# IBL_behavior_control.net
KiCad netlist of a schematic drawn in EAGLE
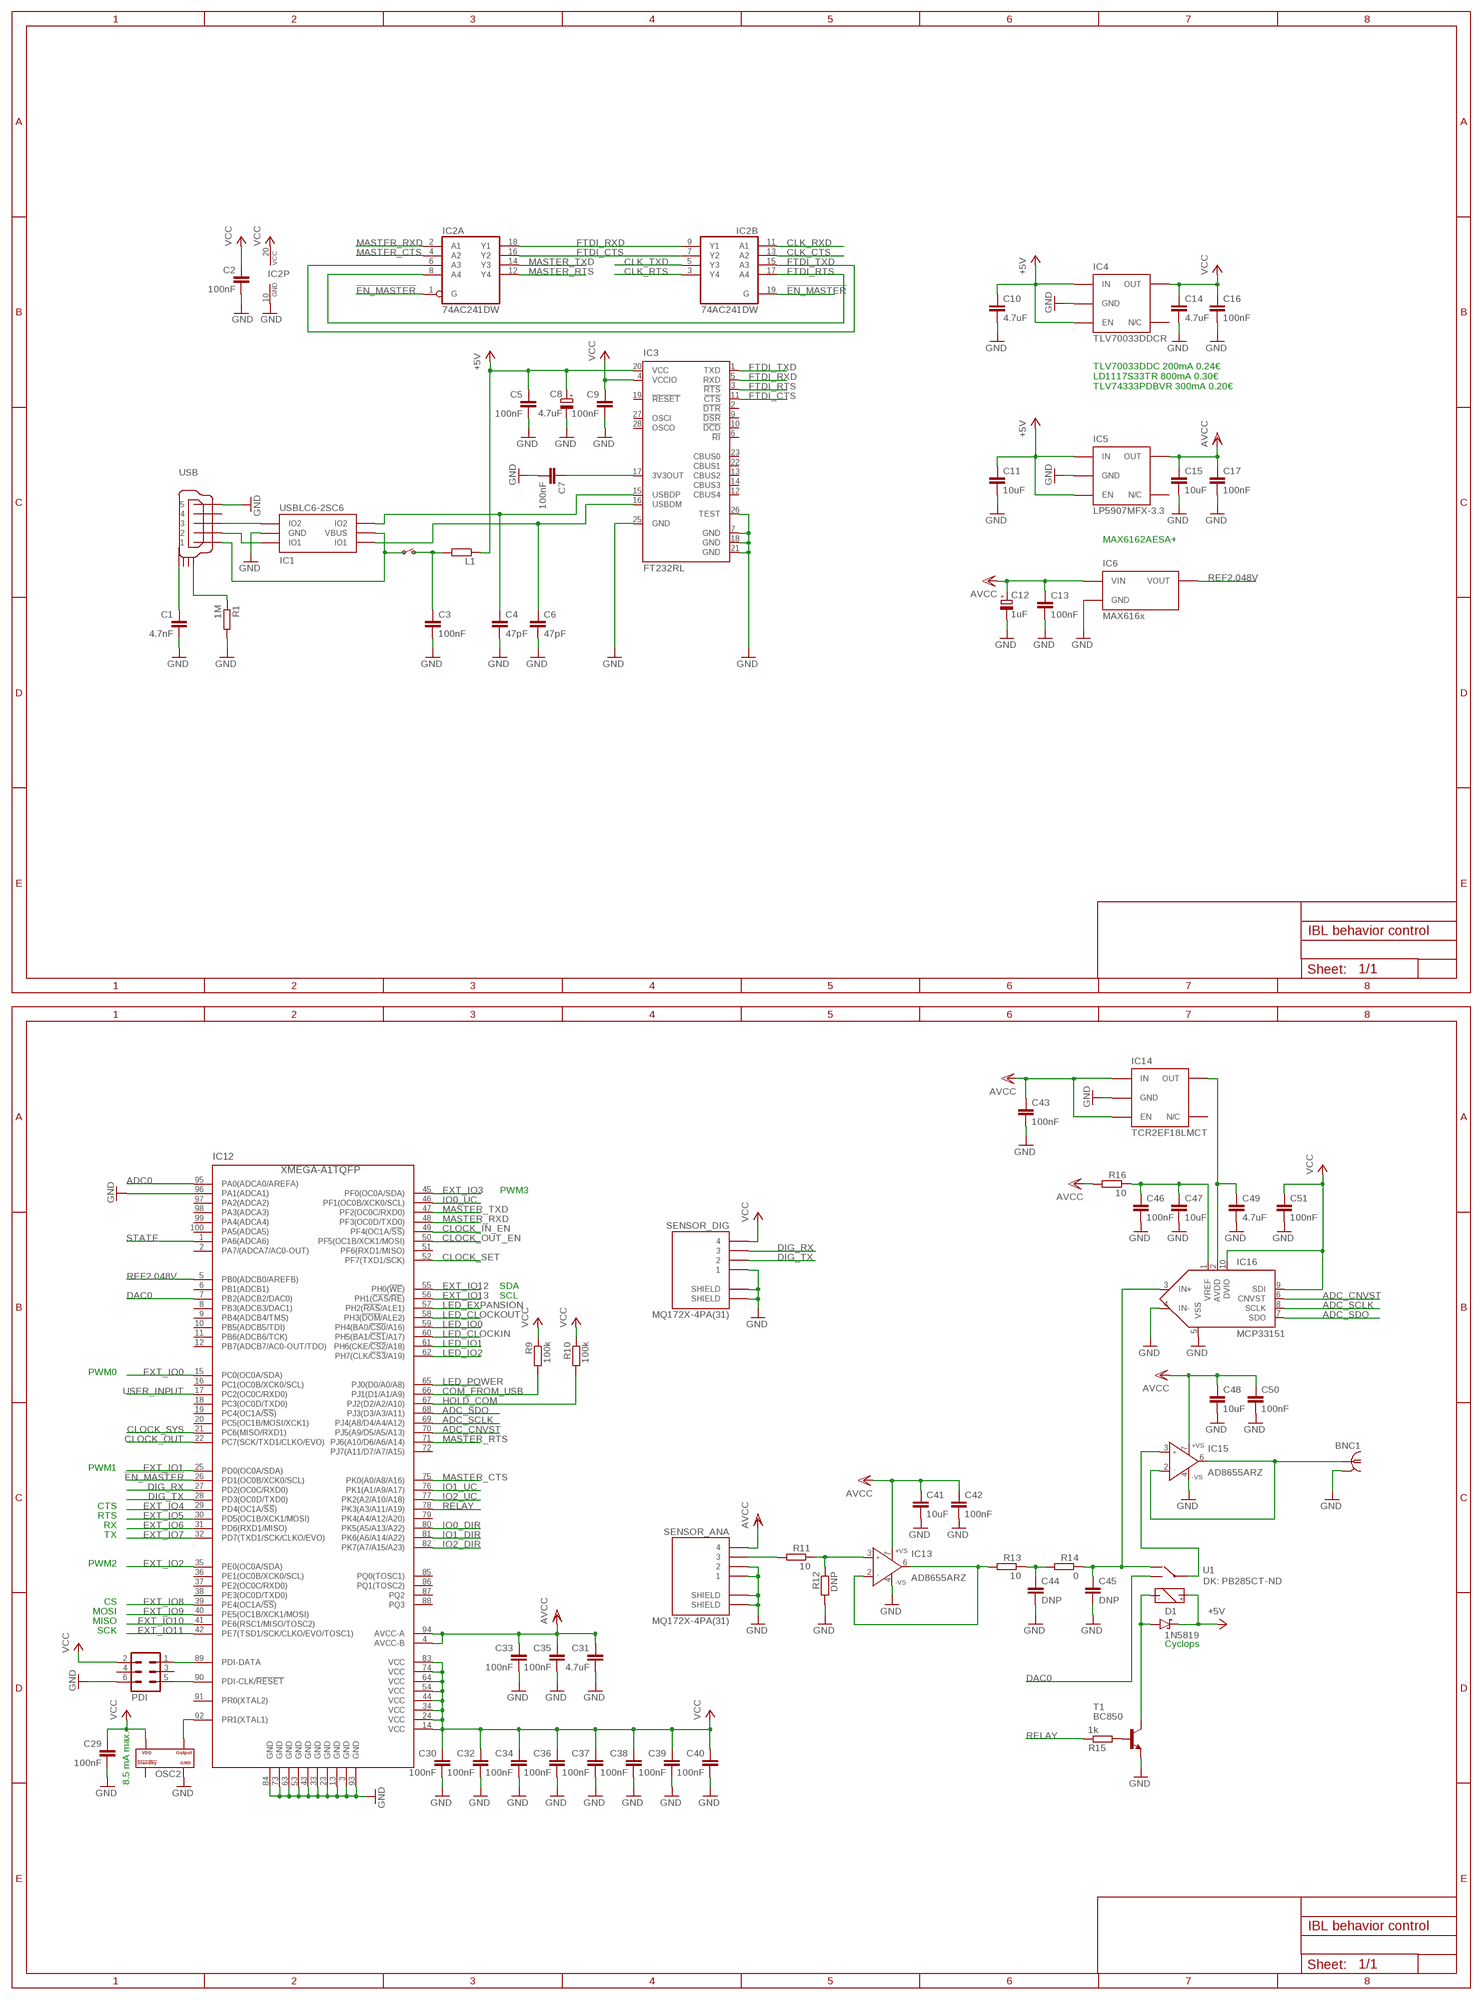
[diagram p0: schematic, sheet 1, part 1 of 2]
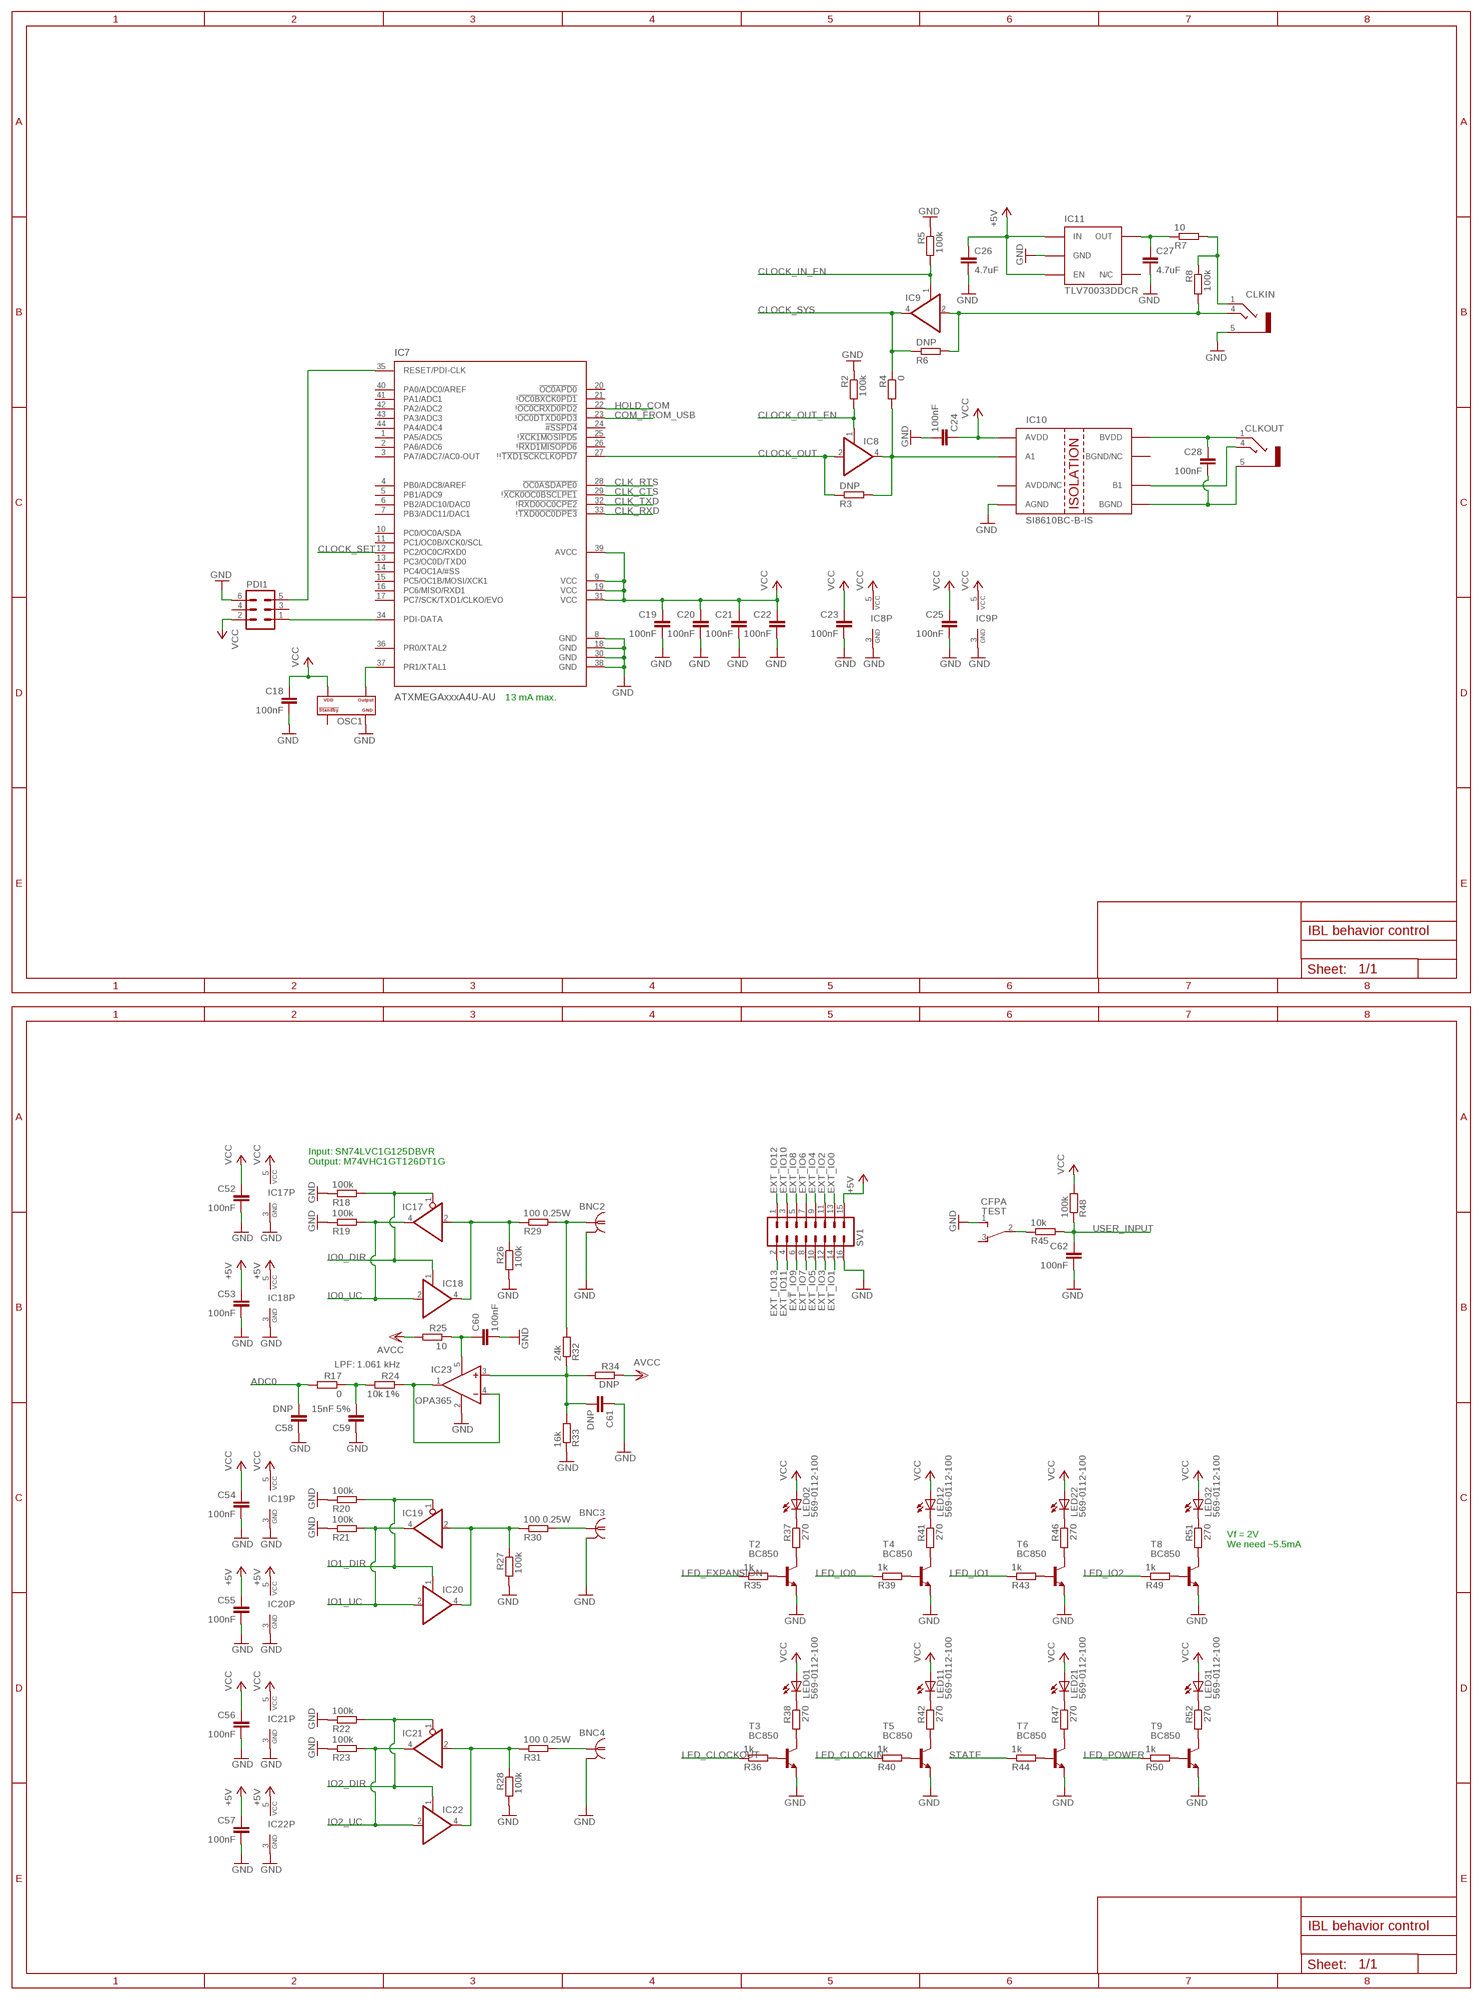
[diagram p1: schematic, sheet 1, part 2 of 2]

(export (version "E")
  (design (tool "Eeschema 10.0.6"))
  (components
    (comp (ref "BNC1")
      (value "BNC_0731000105")
      (footprint "eagle-import:0731000105")
      (libsource (lib "eagle-import") (part "BNC_0731000105"))
    )
    (comp (ref "BNC2")
      (value "BNC_0731000105")
      (footprint "eagle-import:0731000105")
      (libsource (lib "eagle-import") (part "BNC_0731000105"))
    )
    (comp (ref "BNC3")
      (value "BNC_0731000105")
      (footprint "eagle-import:0731000105")
      (libsource (lib "eagle-import") (part "BNC_0731000105"))
    )
    (comp (ref "BNC4")
      (value "BNC_0731000105")
      (footprint "eagle-import:0731000105")
      (libsource (lib "eagle-import") (part "BNC_0731000105"))
    )
    (comp (ref "C1")
      (value "4.7nF")
      (footprint "eagle-import:C0402")
      (libsource (lib "eagle-import") (part "C-EUC0402"))
    )
    (comp (ref "C2")
      (value "100nF")
      (footprint "eagle-import:C0402")
      (libsource (lib "eagle-import") (part "C-EUC0402"))
    )
    (comp (ref "C3")
      (value "100nF")
      (footprint "eagle-import:C0402")
      (libsource (lib "eagle-import") (part "C-EUC0402"))
    )
    (comp (ref "C4")
      (value "47pF")
      (footprint "eagle-import:C0402")
      (libsource (lib "eagle-import") (part "C-EUC0402"))
    )
    (comp (ref "C5")
      (value "100nF")
      (footprint "eagle-import:C0402")
      (libsource (lib "eagle-import") (part "C-EUC0402"))
    )
    (comp (ref "C6")
      (value "47pF")
      (footprint "eagle-import:C0402")
      (libsource (lib "eagle-import") (part "C-EUC0402"))
    )
    (comp (ref "C7")
      (value "100nF")
      (footprint "eagle-import:C0402")
      (libsource (lib "eagle-import") (part "C-EUC0402"))
    )
    (comp (ref "C8")
      (value "4.7uF")
      (footprint "eagle-import:A_3216-18W")
      (libsource (lib "eagle-import") (part "CPOL-EUA/3216-18W"))
    )
    (comp (ref "C9")
      (value "100nF")
      (footprint "eagle-import:C0402")
      (libsource (lib "eagle-import") (part "C-EUC0402"))
    )
    (comp (ref "C10")
      (value "4.7uF")
      (footprint "eagle-import:C0603")
      (libsource (lib "eagle-import") (part "C-EUC0603"))
    )
    (comp (ref "C11")
      (value "10uF")
      (footprint "eagle-import:C0603")
      (libsource (lib "eagle-import") (part "C-EUC0603"))
    )
    (comp (ref "C12")
      (value "1uF")
      (footprint "eagle-import:R_2012-12R")
      (libsource (lib "eagle-import") (part "CPOL-EUR/2012-12R"))
    )
    (comp (ref "C13")
      (value "100nF")
      (footprint "eagle-import:C0402")
      (libsource (lib "eagle-import") (part "C-EUC0402"))
    )
    (comp (ref "C14")
      (value "4.7uF")
      (footprint "eagle-import:C0603")
      (libsource (lib "eagle-import") (part "C-EUC0603"))
    )
    (comp (ref "C15")
      (value "10uF")
      (footprint "eagle-import:C0603")
      (libsource (lib "eagle-import") (part "C-EUC0603"))
    )
    (comp (ref "C16")
      (value "100nF")
      (footprint "eagle-import:C0402")
      (libsource (lib "eagle-import") (part "C-EUC0402"))
    )
    (comp (ref "C17")
      (value "100nF")
      (footprint "eagle-import:C0402")
      (libsource (lib "eagle-import") (part "C-EUC0402"))
    )
    (comp (ref "C18")
      (value "100nF")
      (footprint "eagle-import:C0402")
      (libsource (lib "eagle-import") (part "C-EUC0402"))
    )
    (comp (ref "C19")
      (value "100nF")
      (footprint "eagle-import:C0402")
      (libsource (lib "eagle-import") (part "C-EUC0402"))
    )
    (comp (ref "C20")
      (value "100nF")
      (footprint "eagle-import:C0402")
      (libsource (lib "eagle-import") (part "C-EUC0402"))
    )
    (comp (ref "C21")
      (value "100nF")
      (footprint "eagle-import:C0402")
      (libsource (lib "eagle-import") (part "C-EUC0402"))
    )
    (comp (ref "C22")
      (value "100nF")
      (footprint "eagle-import:C0402")
      (libsource (lib "eagle-import") (part "C-EUC0402"))
    )
    (comp (ref "C23")
      (value "100nF")
      (footprint "eagle-import:C0402")
      (libsource (lib "eagle-import") (part "C-EUC0402"))
    )
    (comp (ref "C24")
      (value "100nF")
      (footprint "eagle-import:C0402")
      (libsource (lib "eagle-import") (part "C-EUC0402"))
    )
    (comp (ref "C25")
      (value "100nF")
      (footprint "eagle-import:C0402")
      (libsource (lib "eagle-import") (part "C-EUC0402"))
    )
    (comp (ref "C26")
      (value "4.7uF")
      (footprint "eagle-import:C0603")
      (libsource (lib "eagle-import") (part "C-EUC0603"))
    )
    (comp (ref "C27")
      (value "4.7uF")
      (footprint "eagle-import:C0603")
      (libsource (lib "eagle-import") (part "C-EUC0603"))
    )
    (comp (ref "C28")
      (value "100nF")
      (footprint "eagle-import:C0402")
      (libsource (lib "eagle-import") (part "C-EUC0402"))
    )
    (comp (ref "C29")
      (value "100nF")
      (footprint "eagle-import:C0402")
      (libsource (lib "eagle-import") (part "C-EUC0402"))
    )
    (comp (ref "C30")
      (value "100nF")
      (footprint "eagle-import:C0402")
      (libsource (lib "eagle-import") (part "C-EUC0402"))
    )
    (comp (ref "C31")
      (value "4.7uF")
      (footprint "eagle-import:C0603")
      (libsource (lib "eagle-import") (part "C-EUC0603"))
    )
    (comp (ref "C32")
      (value "100nF")
      (footprint "eagle-import:C0402")
      (libsource (lib "eagle-import") (part "C-EUC0402"))
    )
    (comp (ref "C33")
      (value "100nF")
      (footprint "eagle-import:C0402")
      (libsource (lib "eagle-import") (part "C-EUC0402"))
    )
    (comp (ref "C34")
      (value "100nF")
      (footprint "eagle-import:C0402")
      (libsource (lib "eagle-import") (part "C-EUC0402"))
    )
    (comp (ref "C35")
      (value "100nF")
      (footprint "eagle-import:C0402")
      (libsource (lib "eagle-import") (part "C-EUC0402"))
    )
    (comp (ref "C36")
      (value "100nF")
      (footprint "eagle-import:C0402")
      (libsource (lib "eagle-import") (part "C-EUC0402"))
    )
    (comp (ref "C37")
      (value "100nF")
      (footprint "eagle-import:C0402")
      (libsource (lib "eagle-import") (part "C-EUC0402"))
    )
    (comp (ref "C38")
      (value "100nF")
      (footprint "eagle-import:C0402")
      (libsource (lib "eagle-import") (part "C-EUC0402"))
    )
    (comp (ref "C39")
      (value "100nF")
      (footprint "eagle-import:C0402")
      (libsource (lib "eagle-import") (part "C-EUC0402"))
    )
    (comp (ref "C40")
      (value "100nF")
      (footprint "eagle-import:C0402")
      (libsource (lib "eagle-import") (part "C-EUC0402"))
    )
    (comp (ref "C41")
      (value "10uF")
      (footprint "eagle-import:C0603")
      (libsource (lib "eagle-import") (part "C-EUC0603"))
    )
    (comp (ref "C42")
      (value "100nF")
      (footprint "eagle-import:C0402")
      (libsource (lib "eagle-import") (part "C-EUC0402"))
    )
    (comp (ref "C43")
      (value "100nF")
      (footprint "eagle-import:C0402")
      (libsource (lib "eagle-import") (part "C-EUC0402"))
    )
    (comp (ref "C44")
      (value "DNP")
      (footprint "eagle-import:C0402")
      (libsource (lib "eagle-import") (part "C-EUC0402"))
    )
    (comp (ref "C45")
      (value "DNP")
      (footprint "eagle-import:C0402")
      (libsource (lib "eagle-import") (part "C-EUC0402"))
    )
    (comp (ref "C46")
      (value "100nF")
      (footprint "eagle-import:C0402")
      (libsource (lib "eagle-import") (part "C-EUC0402"))
    )
    (comp (ref "C47")
      (value "10uF")
      (footprint "eagle-import:C0603")
      (libsource (lib "eagle-import") (part "C-EUC0603"))
    )
    (comp (ref "C48")
      (value "10uF")
      (footprint "eagle-import:C0603")
      (libsource (lib "eagle-import") (part "C-EUC0603"))
    )
    (comp (ref "C49")
      (value "4.7uF")
      (footprint "eagle-import:C0603")
      (libsource (lib "eagle-import") (part "C-EUC0603"))
    )
    (comp (ref "C50")
      (value "100nF")
      (footprint "eagle-import:C0402")
      (libsource (lib "eagle-import") (part "C-EUC0402"))
    )
    (comp (ref "C51")
      (value "100nF")
      (footprint "eagle-import:C0402")
      (libsource (lib "eagle-import") (part "C-EUC0402"))
    )
    (comp (ref "C52")
      (value "100nF")
      (footprint "eagle-import:C0402")
      (libsource (lib "eagle-import") (part "C-EUC0402"))
    )
    (comp (ref "C53")
      (value "100nF")
      (footprint "eagle-import:C0402")
      (libsource (lib "eagle-import") (part "C-EUC0402"))
    )
    (comp (ref "C54")
      (value "100nF")
      (footprint "eagle-import:C0402")
      (libsource (lib "eagle-import") (part "C-EUC0402"))
    )
    (comp (ref "C55")
      (value "100nF")
      (footprint "eagle-import:C0402")
      (libsource (lib "eagle-import") (part "C-EUC0402"))
    )
    (comp (ref "C56")
      (value "100nF")
      (footprint "eagle-import:C0402")
      (libsource (lib "eagle-import") (part "C-EUC0402"))
    )
    (comp (ref "C57")
      (value "100nF")
      (footprint "eagle-import:C0402")
      (libsource (lib "eagle-import") (part "C-EUC0402"))
    )
    (comp (ref "C58")
      (value "DNP")
      (footprint "eagle-import:C0402")
      (libsource (lib "eagle-import") (part "C-EUC0402"))
    )
    (comp (ref "C59")
      (value "15nF 5%")
      (footprint "eagle-import:C0402")
      (libsource (lib "eagle-import") (part "C-EUC0402"))
    )
    (comp (ref "C60")
      (value "100nF")
      (footprint "eagle-import:C0402")
      (libsource (lib "eagle-import") (part "C-EUC0402"))
    )
    (comp (ref "C61")
      (value "DNP")
      (footprint "eagle-import:C0402")
      (libsource (lib "eagle-import") (part "C-EUC0402"))
    )
    (comp (ref "C62")
      (value "100nF")
      (footprint "eagle-import:C0402")
      (libsource (lib "eagle-import") (part "C-EUC0402"))
    )
    (comp (ref "CLKIN")
      (value "STEREO_JACK")
      (footprint "eagle-import:35RASMT2BHNTRX")
      (libsource (lib "eagle-import") (part "STEREO_JACK"))
    )
    (comp (ref "CLKOUT")
      (value "STEREO_JACK")
      (footprint "eagle-import:35RASMT2BHNTRX")
      (libsource (lib "eagle-import") (part "STEREO_JACK"))
    )
    (comp (ref "D1")
      (value "1N5819")
      (footprint "eagle-import:SOD123")
      (libsource (lib "eagle-import") (part "S-DIODESOD-123"))
    )
    (comp (ref "IC1")
      (value "USBLC6-2SC6")
      (footprint "eagle-import:SOT23-6L")
      (libsource (lib "eagle-import") (part "USBLC6-2"))
    )
    (comp (ref "IC2")
      (value "74AC241DW")
      (footprint "eagle-import:SO20W")
      (libsource (lib "eagle-import") (part "74241DWAC"))
    )
    (comp (ref "IC3")
      (value "FT232RL")
      (footprint "eagle-import:SSOP28")
      (libsource (lib "eagle-import") (part "FT232RL"))
    )
    (comp (ref "IC4")
      (value "TLV70033DDCR")
      (footprint "eagle-import:TSOT23-5")
      (libsource (lib "eagle-import") (part "TLV700XX"))
    )
    (comp (ref "IC5")
      (value "LP5907MFX-3.3")
      (footprint "eagle-import:TSOT23-5")
      (libsource (lib "eagle-import") (part "TLV700XX"))
    )
    (comp (ref "IC6")
      (value "MAX616x")
      (footprint "eagle-import:SO-08")
      (libsource (lib "eagle-import") (part "ADR45XX"))
    )
    (comp (ref "IC7")
      (value "ATXMEGAxxxA4U-AU")
      (footprint "eagle-import:QFP80P1200X1200X120-44N")
      (libsource (lib "eagle-import") (part "AT-XMEGA-XXA4-AU"))
    )
    (comp (ref "IC8")
      (value "74AHC1G126DCK")
      (footprint "eagle-import:SC70-5")
      (libsource (lib "eagle-import") (part "741G126DCKAHC"))
    )
    (comp (ref "IC9")
      (value "74AHC1G126DCK")
      (footprint "eagle-import:SC70-5")
      (libsource (lib "eagle-import") (part "741G126DCKAHC"))
    )
    (comp (ref "IC10")
      (value "SI8610BC-B-IS")
      (footprint "eagle-import:SO-08")
      (libsource (lib "eagle-import") (part "SI8610"))
    )
    (comp (ref "IC11")
      (value "TLV70033DDCR")
      (footprint "eagle-import:TSOT23-5")
      (libsource (lib "eagle-import") (part "TLV700XX"))
    )
    (comp (ref "IC12")
      (value "XMEGA-A1TQFP")
      (footprint "eagle-import:TQFP100")
      (libsource (lib "eagle-import") (part "XMEGA-A1TQFP"))
    )
    (comp (ref "IC13")
      (value "AD8655ARZ")
      (footprint "eagle-import:SO8")
      (fields (field (name "MF") "ALTERA CORPORATION") (field (name "MPN") "AD8655ARMZ-REEL"))
      (libsource (lib "eagle-import") (part "AD8655R"))
    )
    (comp (ref "IC14")
      (value "TCR2EF18LMCT")
      (footprint "eagle-import:TSOT23-5")
      (libsource (lib "eagle-import") (part "TLV700XX"))
    )
    (comp (ref "IC15")
      (value "AD8655ARZ")
      (footprint "eagle-import:SO8")
      (fields (field (name "MF") "ALTERA CORPORATION") (field (name "MPN") "AD8655ARMZ-REEL"))
      (libsource (lib "eagle-import") (part "AD8655R"))
    )
    (comp (ref "IC16")
      (value "MCP33151")
      (footprint "eagle-import:MSOP10")
      (libsource (lib "eagle-import") (part "MCP33151"))
    )
    (comp (ref "IC17")
      (value "74AHC1G125DBV")
      (footprint "eagle-import:SOT23-5")
      (libsource (lib "eagle-import") (part "741G125DBVAHC"))
    )
    (comp (ref "IC18")
      (value "74AHC1G126DCK")
      (footprint "eagle-import:SC70-5")
      (libsource (lib "eagle-import") (part "741G126DCKAHC"))
    )
    (comp (ref "IC19")
      (value "74AHC1G125DBV")
      (footprint "eagle-import:SOT23-5")
      (libsource (lib "eagle-import") (part "741G125DBVAHC"))
    )
    (comp (ref "IC20")
      (value "74AHC1G126DCK")
      (footprint "eagle-import:SC70-5")
      (libsource (lib "eagle-import") (part "741G126DCKAHC"))
    )
    (comp (ref "IC21")
      (value "74AHC1G125DBV")
      (footprint "eagle-import:SOT23-5")
      (libsource (lib "eagle-import") (part "741G125DBVAHC"))
    )
    (comp (ref "IC22")
      (value "74AHC1G126DCK")
      (footprint "eagle-import:SC70-5")
      (libsource (lib "eagle-import") (part "741G126DCKAHC"))
    )
    (comp (ref "IC23")
      (value "OPA365")
      (footprint "eagle-import:SOT23-5")
      (libsource (lib "eagle-import") (part "OPA365"))
    )
    (comp (ref "L1")
      (value "???")
      (footprint "eagle-import:R0805")
      (libsource (lib "eagle-import") (part "R-EU_R0805"))
    )
    (comp (ref "LED0")
      (value "569-0112-100")
      (footprint "eagle-import:569-011X-X00_LED_ARRAY")
      (libsource (lib "eagle-import") (part "LED_2X_VERTICAL"))
    )
    (comp (ref "LED1")
      (value "569-0112-100")
      (footprint "eagle-import:569-011X-X00_LED_ARRAY")
      (libsource (lib "eagle-import") (part "LED_2X_VERTICAL"))
    )
    (comp (ref "LED2")
      (value "569-0112-100")
      (footprint "eagle-import:569-011X-X00_LED_ARRAY")
      (libsource (lib "eagle-import") (part "LED_2X_VERTICAL"))
    )
    (comp (ref "LED3")
      (value "569-0112-100")
      (footprint "eagle-import:569-011X-X00_LED_ARRAY")
      (libsource (lib "eagle-import") (part "LED_2X_VERTICAL"))
    )
    (comp (ref "OSC1")
      (value "OSCILLATOR")
      (footprint "eagle-import:OSCILLATOR_3.2X2.5")
      (libsource (lib "eagle-import") (part "OSCILLATOR"))
    )
    (comp (ref "OSC2")
      (value "OSCILLATOR")
      (footprint "eagle-import:OSCILLATOR_3.2X2.5")
      (libsource (lib "eagle-import") (part "OSCILLATOR"))
    )
    (comp (ref "PDI")
      (value "MA03-2")
      (footprint "eagle-import:MA03-2")
      (libsource (lib "eagle-import") (part "MA03-2"))
    )
    (comp (ref "PDI1")
      (value "MA03-2")
      (footprint "eagle-import:MA03-2")
      (libsource (lib "eagle-import") (part "MA03-2"))
    )
    (comp (ref "R1")
      (value "1M")
      (footprint "eagle-import:R0402")
      (libsource (lib "eagle-import") (part "R-EU_R0402"))
    )
    (comp (ref "R2")
      (value "100k")
      (footprint "eagle-import:R0402")
      (libsource (lib "eagle-import") (part "R-EU_R0402"))
    )
    (comp (ref "R3")
      (value "DNP")
      (footprint "eagle-import:R0402")
      (libsource (lib "eagle-import") (part "R-EU_R0402"))
    )
    (comp (ref "R4")
      (value "0")
      (footprint "eagle-import:R0402")
      (libsource (lib "eagle-import") (part "R-EU_R0402"))
    )
    (comp (ref "R5")
      (value "100k")
      (footprint "eagle-import:R0402")
      (libsource (lib "eagle-import") (part "R-EU_R0402"))
    )
    (comp (ref "R6")
      (value "DNP")
      (footprint "eagle-import:R0402")
      (libsource (lib "eagle-import") (part "R-EU_R0402"))
    )
    (comp (ref "R7")
      (value "10")
      (footprint "eagle-import:R0402")
      (libsource (lib "eagle-import") (part "R-EU_R0402"))
    )
    (comp (ref "R8")
      (value "100k")
      (footprint "eagle-import:R0402")
      (libsource (lib "eagle-import") (part "R-EU_R0402"))
    )
    (comp (ref "R9")
      (value "100k")
      (footprint "eagle-import:R0402")
      (libsource (lib "eagle-import") (part "R-EU_R0402"))
    )
    (comp (ref "R10")
      (value "100k")
      (footprint "eagle-import:R0402")
      (libsource (lib "eagle-import") (part "R-EU_R0402"))
    )
    (comp (ref "R11")
      (value "10")
      (footprint "eagle-import:R0402")
      (libsource (lib "eagle-import") (part "R-EU_R0402"))
    )
    (comp (ref "R12")
      (value "DNP")
      (footprint "eagle-import:R0402")
      (libsource (lib "eagle-import") (part "R-EU_R0402"))
    )
    (comp (ref "R13")
      (value "10")
      (footprint "eagle-import:R0402")
      (libsource (lib "eagle-import") (part "R-EU_R0402"))
    )
    (comp (ref "R14")
      (value "0")
      (footprint "eagle-import:R0402")
      (libsource (lib "eagle-import") (part "R-EU_R0402"))
    )
    (comp (ref "R15")
      (value "1k")
      (footprint "eagle-import:R0402")
      (libsource (lib "eagle-import") (part "R-EU_R0402"))
    )
    (comp (ref "R16")
      (value "10")
      (footprint "eagle-import:R0402")
      (libsource (lib "eagle-import") (part "R-EU_R0402"))
    )
    (comp (ref "R17")
      (value "0")
      (footprint "eagle-import:R0402")
      (libsource (lib "eagle-import") (part "R-EU_R0402"))
    )
    (comp (ref "R18")
      (value "100k")
      (footprint "eagle-import:R0402")
      (libsource (lib "eagle-import") (part "R-EU_R0402"))
    )
    (comp (ref "R19")
      (value "100k")
      (footprint "eagle-import:R0402")
      (libsource (lib "eagle-import") (part "R-EU_R0402"))
    )
    (comp (ref "R20")
      (value "100k")
      (footprint "eagle-import:R0402")
      (libsource (lib "eagle-import") (part "R-EU_R0402"))
    )
    (comp (ref "R21")
      (value "100k")
      (footprint "eagle-import:R0402")
      (libsource (lib "eagle-import") (part "R-EU_R0402"))
    )
    (comp (ref "R22")
      (value "100k")
      (footprint "eagle-import:R0402")
      (libsource (lib "eagle-import") (part "R-EU_R0402"))
    )
    (comp (ref "R23")
      (value "100k")
      (footprint "eagle-import:R0402")
      (libsource (lib "eagle-import") (part "R-EU_R0402"))
    )
    (comp (ref "R24")
      (value "10k 1%")
      (footprint "eagle-import:R0402")
      (libsource (lib "eagle-import") (part "R-EU_R0402"))
    )
    (comp (ref "R25")
      (value "10")
      (footprint "eagle-import:R0402")
      (libsource (lib "eagle-import") (part "R-EU_R0402"))
    )
    (comp (ref "R26")
      (value "100k")
      (footprint "eagle-import:R0402")
      (libsource (lib "eagle-import") (part "R-EU_R0402"))
    )
    (comp (ref "R27")
      (value "100k")
      (footprint "eagle-import:R0402")
      (libsource (lib "eagle-import") (part "R-EU_R0402"))
    )
    (comp (ref "R28")
      (value "100k")
      (footprint "eagle-import:R0402")
      (libsource (lib "eagle-import") (part "R-EU_R0402"))
    )
    (comp (ref "R29")
      (value "100 0.25W")
      (footprint "eagle-import:R0603")
      (libsource (lib "eagle-import") (part "R-EU_R0603"))
    )
    (comp (ref "R30")
      (value "100 0.25W")
      (footprint "eagle-import:R0603")
      (libsource (lib "eagle-import") (part "R-EU_R0603"))
    )
    (comp (ref "R31")
      (value "100 0.25W")
      (footprint "eagle-import:R0603")
      (libsource (lib "eagle-import") (part "R-EU_R0603"))
    )
    (comp (ref "R32")
      (value "24k")
      (footprint "eagle-import:R0402")
      (libsource (lib "eagle-import") (part "R-EU_R0402"))
    )
    (comp (ref "R33")
      (value "16k")
      (footprint "eagle-import:R0402")
      (libsource (lib "eagle-import") (part "R-EU_R0402"))
    )
    (comp (ref "R34")
      (value "DNP")
      (footprint "eagle-import:R0402")
      (libsource (lib "eagle-import") (part "R-EU_R0402"))
    )
    (comp (ref "R35")
      (value "1k")
      (footprint "eagle-import:R0402")
      (libsource (lib "eagle-import") (part "R-EU_R0402"))
    )
    (comp (ref "R36")
      (value "1k")
      (footprint "eagle-import:R0402")
      (libsource (lib "eagle-import") (part "R-EU_R0402"))
    )
    (comp (ref "R37")
      (value "270")
      (footprint "eagle-import:R0402")
      (libsource (lib "eagle-import") (part "R-EU_R0402"))
    )
    (comp (ref "R38")
      (value "270")
      (footprint "eagle-import:R0402")
      (libsource (lib "eagle-import") (part "R-EU_R0402"))
    )
    (comp (ref "R39")
      (value "1k")
      (footprint "eagle-import:R0402")
      (libsource (lib "eagle-import") (part "R-EU_R0402"))
    )
    (comp (ref "R40")
      (value "1k")
      (footprint "eagle-import:R0402")
      (libsource (lib "eagle-import") (part "R-EU_R0402"))
    )
    (comp (ref "R41")
      (value "270")
      (footprint "eagle-import:R0402")
      (libsource (lib "eagle-import") (part "R-EU_R0402"))
    )
    (comp (ref "R42")
      (value "270")
      (footprint "eagle-import:R0402")
      (libsource (lib "eagle-import") (part "R-EU_R0402"))
    )
    (comp (ref "R43")
      (value "1k")
      (footprint "eagle-import:R0402")
      (libsource (lib "eagle-import") (part "R-EU_R0402"))
    )
    (comp (ref "R44")
      (value "1k")
      (footprint "eagle-import:R0402")
      (libsource (lib "eagle-import") (part "R-EU_R0402"))
    )
    (comp (ref "R45")
      (value "10k")
      (footprint "eagle-import:R0402")
      (libsource (lib "eagle-import") (part "R-EU_R0402"))
    )
    (comp (ref "R46")
      (value "270")
      (footprint "eagle-import:R0402")
      (libsource (lib "eagle-import") (part "R-EU_R0402"))
    )
    (comp (ref "R47")
      (value "270")
      (footprint "eagle-import:R0402")
      (libsource (lib "eagle-import") (part "R-EU_R0402"))
    )
    (comp (ref "R48")
      (value "100k")
      (footprint "eagle-import:R0402")
      (libsource (lib "eagle-import") (part "R-EU_R0402"))
    )
    (comp (ref "R49")
      (value "1k")
      (footprint "eagle-import:R0402")
      (libsource (lib "eagle-import") (part "R-EU_R0402"))
    )
    (comp (ref "R50")
      (value "1k")
      (footprint "eagle-import:R0402")
      (libsource (lib "eagle-import") (part "R-EU_R0402"))
    )
    (comp (ref "R51")
      (value "270")
      (footprint "eagle-import:R0402")
      (libsource (lib "eagle-import") (part "R-EU_R0402"))
    )
    (comp (ref "R52")
      (value "270")
      (footprint "eagle-import:R0402")
      (libsource (lib "eagle-import") (part "R-EU_R0402"))
    )
    (comp (ref "SENSOR_ANA")
      (value "MQ172X-4PA(31)")
      (footprint "eagle-import:MQ172X-4PA(31)")
      (libsource (lib "eagle-import") (part "MQ172X-4PA(31)"))
    )
    (comp (ref "SENSOR_DIG")
      (value "MQ172X-4PA(31)")
      (footprint "eagle-import:MQ172X-4PA(31)")
      (libsource (lib "eagle-import") (part "MQ172X-4PA(31)"))
    )
    (comp (ref "SV1")
      (value "ML16L")
      (footprint "eagle-import:ML16L")
      (libsource (lib "eagle-import") (part "ML16L"))
    )
    (comp (ref "T1")
      (value "BC850")
      (footprint "eagle-import:SOT23")
      (libsource (lib "eagle-import") (part "BC850"))
    )
    (comp (ref "T2")
      (value "BC850")
      (footprint "eagle-import:SOT23")
      (libsource (lib "eagle-import") (part "BC850"))
    )
    (comp (ref "T3")
      (value "BC850")
      (footprint "eagle-import:SOT23")
      (libsource (lib "eagle-import") (part "BC850"))
    )
    (comp (ref "T4")
      (value "BC850")
      (footprint "eagle-import:SOT23")
      (libsource (lib "eagle-import") (part "BC850"))
    )
    (comp (ref "T5")
      (value "BC850")
      (footprint "eagle-import:SOT23")
      (libsource (lib "eagle-import") (part "BC850"))
    )
    (comp (ref "T6")
      (value "BC850")
      (footprint "eagle-import:SOT23")
      (libsource (lib "eagle-import") (part "BC850"))
    )
    (comp (ref "T7")
      (value "BC850")
      (footprint "eagle-import:SOT23")
      (libsource (lib "eagle-import") (part "BC850"))
    )
    (comp (ref "T8")
      (value "BC850")
      (footprint "eagle-import:SOT23")
      (libsource (lib "eagle-import") (part "BC850"))
    )
    (comp (ref "T9")
      (value "BC850")
      (footprint "eagle-import:SOT23")
      (libsource (lib "eagle-import") (part "BC850"))
    )
    (comp (ref "TEST")
      (value "CFPA")
      (footprint "eagle-import:CFPA")
      (libsource (lib "eagle-import") (part "SPDT_CFPA"))
    )
    (comp (ref "U1")
      (value "DK: PB285CT-ND")
      (footprint "eagle-import:RELAY")
      (libsource (lib "eagle-import") (part "RELAY"))
    )
    (comp (ref "USB")
      (value "USB_MINI_B")
      (footprint "eagle-import:240-0002-1")
      (libsource (lib "eagle-import") (part "USB_MINI_B"))
    )
  )
  (nets
    (net (code "1") (name "+5V") (class "Default")
      (node (ref "C10") (pin "1") (pinfunction "1_1") (pintype "passive"))
      (node (ref "C11") (pin "1") (pinfunction "1_1") (pintype "passive"))
      (node (ref "C26") (pin "1") (pinfunction "1_1") (pintype "passive"))
      (node (ref "C5") (pin "1") (pinfunction "1_1") (pintype "passive"))
      (node (ref "C53") (pin "1") (pinfunction "1_1") (pintype "passive"))
      (node (ref "C55") (pin "1") (pinfunction "1_1") (pintype "passive"))
      (node (ref "C57") (pin "1") (pinfunction "1_1") (pintype "passive"))
      (node (ref "C8") (pin "+") (pinfunction "+_+") (pintype "passive"))
      (node (ref "D1") (pin "C") (pinfunction "C_C") (pintype "passive"))
      (node (ref "IC11") (pin "1") (pinfunction "IN_1") (pintype "bidirectional"))
      (node (ref "IC11") (pin "3") (pinfunction "EN_3") (pintype "bidirectional"))
      (node (ref "IC18") (pin "5") (pinfunction "VCC_5") (pintype "power_in"))
      (node (ref "IC20") (pin "5") (pinfunction "VCC_5") (pintype "power_in"))
      (node (ref "IC22") (pin "5") (pinfunction "VCC_5") (pintype "power_in"))
      (node (ref "IC3") (pin "20") (pinfunction "VCC_20") (pintype "power_in"))
      (node (ref "IC4") (pin "1") (pinfunction "IN_1") (pintype "bidirectional"))
      (node (ref "IC4") (pin "3") (pinfunction "EN_3") (pintype "bidirectional"))
      (node (ref "IC5") (pin "1") (pinfunction "IN_1") (pintype "bidirectional"))
      (node (ref "IC5") (pin "3") (pinfunction "EN_3") (pintype "bidirectional"))
      (node (ref "L1") (pin "1") (pinfunction "1_1") (pintype "passive"))
      (node (ref "SV1") (pin "15") (pinfunction "15_15") (pintype "passive"))
      (node (ref "U1") (pin "3") (pinfunction "R+_3") (pintype "passive"))
    )
    (net (code "2") (name "/ADC0") (class "Default")
      (node (ref "C58") (pin "2") (pinfunction "2_2") (pintype "passive"))
      (node (ref "IC12") (pin "95") (pinfunction "PA0(ADCA0/AREFA)_95") (pintype "bidirectional"))
      (node (ref "R17") (pin "2") (pinfunction "2_2") (pintype "passive"))
    )
    (net (code "3") (name "/ADC_CNVST") (class "Default")
      (node (ref "IC12") (pin "70") (pinfunction "PJ5(A9/D5/A5/A13)_70") (pintype "bidirectional"))
      (node (ref "IC16") (pin "6") (pinfunction "CNVST_6") (pintype "input"))
    )
    (net (code "4") (name "/ADC_SCLK") (class "Default")
      (node (ref "IC12") (pin "69") (pinfunction "PJ4(A8/D4/A4/A12)_69") (pintype "bidirectional"))
      (node (ref "IC16") (pin "8") (pinfunction "SCLK_8") (pintype "input"))
    )
    (net (code "5") (name "/ADC_SDO") (class "Default")
      (node (ref "IC12") (pin "68") (pinfunction "PJ3(D3/A3/A11)_68") (pintype "bidirectional"))
      (node (ref "IC16") (pin "7") (pinfunction "SDO_7") (pintype "output"))
    )
    (net (code "6") (name "/CLK_CTS") (class "Default")
      (node (ref "IC2") (pin "13") (pinfunction "A2_13") (pintype "input"))
      (node (ref "IC7") (pin "29") (pinfunction "~XCK0OC0BSCLPE1_29") (pintype "bidirectional"))
    )
    (net (code "7") (name "/CLK_RTS") (class "Default")
      (node (ref "IC2") (pin "3") (pinfunction "Y4_3") (pintype "tri_state"))
      (node (ref "IC7") (pin "28") (pinfunction "~{OC0ASDAPE0}_28") (pintype "bidirectional"))
    )
    (net (code "8") (name "/CLK_RXD") (class "Default")
      (node (ref "IC2") (pin "11") (pinfunction "A1_11") (pintype "input"))
      (node (ref "IC7") (pin "33") (pinfunction "~TXD0OC0DPE3_33") (pintype "bidirectional"))
    )
    (net (code "9") (name "/CLK_TXD") (class "Default")
      (node (ref "IC2") (pin "5") (pinfunction "Y3_5") (pintype "tri_state"))
      (node (ref "IC7") (pin "32") (pinfunction "~RXD0OC0CPE2_32") (pintype "bidirectional"))
    )
    (net (code "10") (name "/CLOCK_IN_EN") (class "Default")
      (node (ref "IC12") (pin "49") (pinfunction "PF4(OC1A/~{SS})_49") (pintype "bidirectional"))
      (node (ref "IC9") (pin "1") (pinfunction "OE_1") (pintype "input"))
      (node (ref "R5") (pin "2") (pinfunction "2_2") (pintype "passive"))
    )
    (net (code "11") (name "/CLOCK_OUT") (class "Default")
      (node (ref "IC12") (pin "22") (pinfunction "PC7(SCK/TXD1/CLKO/EVO)_22") (pintype "bidirectional"))
      (node (ref "IC7") (pin "27") (pinfunction "~~{TXD1SCKCLKOPD7}_27") (pintype "bidirectional"))
      (node (ref "IC8") (pin "2") (pinfunction "I_2") (pintype "input"))
      (node (ref "R3") (pin "1") (pinfunction "1_1") (pintype "passive"))
    )
    (net (code "12") (name "/CLOCK_OUT_EN") (class "Default")
      (node (ref "IC12") (pin "50") (pinfunction "PF5(OC1B/XCK1/MOSI)_50") (pintype "bidirectional"))
      (node (ref "IC8") (pin "1") (pinfunction "OE_1") (pintype "input"))
      (node (ref "R2") (pin "2") (pinfunction "2_2") (pintype "passive"))
    )
    (net (code "13") (name "/CLOCK_SET") (class "Default")
      (node (ref "IC12") (pin "52") (pinfunction "PF7(TXD1/SCK)_52") (pintype "bidirectional"))
      (node (ref "IC7") (pin "12") (pinfunction "PC2/OC0C/RXD0_12") (pintype "bidirectional"))
    )
    (net (code "14") (name "/CLOCK_SYS") (class "Default")
      (node (ref "IC12") (pin "21") (pinfunction "PC6(MISO/RXD1)_21") (pintype "bidirectional"))
      (node (ref "IC9") (pin "4") (pinfunction "O_4") (pintype "output"))
      (node (ref "R4") (pin "1") (pinfunction "1_1") (pintype "passive"))
      (node (ref "R6") (pin "1") (pinfunction "1_1") (pintype "passive"))
    )
    (net (code "15") (name "/COM_FROM_USB") (class "Default")
      (node (ref "IC12") (pin "66") (pinfunction "PJ1(D1/A1/A9)_66") (pintype "bidirectional"))
      (node (ref "IC7") (pin "23") (pinfunction "~OC0DTXD0PD3_23") (pintype "bidirectional"))
      (node (ref "R9") (pin "2") (pinfunction "2_2") (pintype "passive"))
    )
    (net (code "16") (name "/DAC0") (class "Default")
      (node (ref "IC12") (pin "7") (pinfunction "PB2(ADCB2/DAC0)_7") (pintype "bidirectional"))
      (node (ref "U1") (pin "10") (pinfunction "NO_10") (pintype "passive"))
    )
    (net (code "17") (name "/DIG_RX") (class "Default")
      (node (ref "IC12") (pin "27") (pinfunction "PD2(OC0C/RXD0)_27") (pintype "bidirectional"))
      (node (ref "SENSOR_DIG") (pin "3") (pinfunction "3_3") (pintype "bidirectional"))
    )
    (net (code "18") (name "/DIG_TX") (class "Default")
      (node (ref "IC12") (pin "28") (pinfunction "PD3(OC0D/TXD0)_28") (pintype "bidirectional"))
      (node (ref "SENSOR_DIG") (pin "2") (pinfunction "2_2") (pintype "bidirectional"))
    )
    (net (code "19") (name "/EXT_IO0") (class "Default")
      (node (ref "IC12") (pin "15") (pinfunction "PC0(OC0A/SDA)_15") (pintype "bidirectional"))
      (node (ref "SV1") (pin "13") (pinfunction "13_13") (pintype "passive"))
    )
    (net (code "20") (name "/EXT_IO1") (class "Default")
      (node (ref "IC12") (pin "25") (pinfunction "PD0(OC0A/SDA)_25") (pintype "bidirectional"))
      (node (ref "SV1") (pin "14") (pinfunction "14_14") (pintype "passive"))
    )
    (net (code "21") (name "/EXT_IO2") (class "Default")
      (node (ref "IC12") (pin "35") (pinfunction "PE0(OC0A/SDA)_35") (pintype "bidirectional"))
      (node (ref "SV1") (pin "11") (pinfunction "11_11") (pintype "passive"))
    )
    (net (code "22") (name "/EXT_IO3") (class "Default")
      (node (ref "IC12") (pin "45") (pinfunction "PF0(OC0A/SDA)_45") (pintype "bidirectional"))
      (node (ref "SV1") (pin "12") (pinfunction "12_12") (pintype "passive"))
    )
    (net (code "23") (name "/EXT_IO4") (class "Default")
      (node (ref "IC12") (pin "29") (pinfunction "PD4(OC1A/~{SS})_29") (pintype "bidirectional"))
      (node (ref "SV1") (pin "9") (pinfunction "9_9") (pintype "passive"))
    )
    (net (code "24") (name "/EXT_IO5") (class "Default")
      (node (ref "IC12") (pin "30") (pinfunction "PD5(OC1B/XCK1/MOSI)_30") (pintype "bidirectional"))
      (node (ref "SV1") (pin "10") (pinfunction "10_10") (pintype "passive"))
    )
    (net (code "25") (name "/EXT_IO6") (class "Default")
      (node (ref "IC12") (pin "31") (pinfunction "PD6(RXD1/MISO)_31") (pintype "bidirectional"))
      (node (ref "SV1") (pin "7") (pinfunction "7_7") (pintype "passive"))
    )
    (net (code "26") (name "/EXT_IO7") (class "Default")
      (node (ref "IC12") (pin "32") (pinfunction "PD7(TXD1/SCK/CLKO/EVO)_32") (pintype "bidirectional"))
      (node (ref "SV1") (pin "8") (pinfunction "8_8") (pintype "passive"))
    )
    (net (code "27") (name "/EXT_IO8") (class "Default")
      (node (ref "IC12") (pin "39") (pinfunction "PE4(OC1A/~{SS})_39") (pintype "bidirectional"))
      (node (ref "SV1") (pin "5") (pinfunction "5_5") (pintype "passive"))
    )
    (net (code "28") (name "/EXT_IO9") (class "Default")
      (node (ref "IC12") (pin "40") (pinfunction "PE5(OC1B/XCK1/MOSI)_40") (pintype "bidirectional"))
      (node (ref "SV1") (pin "6") (pinfunction "6_6") (pintype "passive"))
    )
    (net (code "29") (name "/EXT_IO10") (class "Default")
      (node (ref "IC12") (pin "41") (pinfunction "PE6(RSC1/MISO/TOSC2)_41") (pintype "bidirectional"))
      (node (ref "SV1") (pin "3") (pinfunction "3_3") (pintype "passive"))
    )
    (net (code "30") (name "/EXT_IO11") (class "Default")
      (node (ref "IC12") (pin "42") (pinfunction "PE7(TSD1/SCK/CLKO/EVO/TOSC1)_42") (pintype "bidirectional"))
      (node (ref "SV1") (pin "4") (pinfunction "4_4") (pintype "passive"))
    )
    (net (code "31") (name "/EXT_IO12") (class "Default")
      (node (ref "IC12") (pin "55") (pinfunction "PH0(~{WE})_55") (pintype "bidirectional"))
      (node (ref "SV1") (pin "1") (pinfunction "1_1") (pintype "passive"))
    )
    (net (code "32") (name "/EXT_IO13") (class "Default")
      (node (ref "IC12") (pin "56") (pinfunction "PH1(~{CAS}/~{RE})_56") (pintype "bidirectional"))
      (node (ref "SV1") (pin "2") (pinfunction "2_2") (pintype "passive"))
    )
    (net (code "33") (name "/FTDI_CTS") (class "Default")
      (node (ref "IC2") (pin "16") (pinfunction "Y2_16") (pintype "tri_state"))
      (node (ref "IC2") (pin "7") (pinfunction "Y2_7") (pintype "tri_state"))
      (node (ref "IC3") (pin "11") (pinfunction "~{CTS}_11") (pintype "input"))
    )
    (net (code "34") (name "/FTDI_RTS") (class "Default")
      (node (ref "IC2") (pin "17") (pinfunction "A4_17") (pintype "input"))
      (node (ref "IC2") (pin "8") (pinfunction "A4_8") (pintype "input"))
      (node (ref "IC3") (pin "3") (pinfunction "~{RTS}_3") (pintype "output"))
    )
    (net (code "35") (name "/FTDI_RXD") (class "Default")
      (node (ref "IC2") (pin "18") (pinfunction "Y1_18") (pintype "tri_state"))
      (node (ref "IC2") (pin "9") (pinfunction "Y1_9") (pintype "tri_state"))
      (node (ref "IC3") (pin "5") (pinfunction "RXD_5") (pintype "input"))
    )
    (net (code "36") (name "/FTDI_TXD") (class "Default")
      (node (ref "IC2") (pin "15") (pinfunction "A3_15") (pintype "input"))
      (node (ref "IC2") (pin "6") (pinfunction "A3_6") (pintype "input"))
      (node (ref "IC3") (pin "1") (pinfunction "TXD_1") (pintype "output"))
    )
    (net (code "37") (name "/HOLD_COM") (class "Default")
      (node (ref "IC12") (pin "67") (pinfunction "PJ2(D2/A2/A10)_67") (pintype "bidirectional"))
      (node (ref "IC7") (pin "22") (pinfunction "~OC0CRXD0PD2_22") (pintype "bidirectional"))
      (node (ref "R10") (pin "2") (pinfunction "2_2") (pintype "passive"))
    )
    (net (code "38") (name "/IO0_DIR") (class "Default")
      (node (ref "IC12") (pin "80") (pinfunction "PK5(A5/A13/A22)_80") (pintype "bidirectional"))
      (node (ref "IC17") (pin "1") (pinfunction "OE_1") (pintype "input"))
      (node (ref "IC18") (pin "1") (pinfunction "OE_1") (pintype "input"))
      (node (ref "R18") (pin "2") (pinfunction "2_2") (pintype "passive"))
    )
    (net (code "39") (name "/IO0_UC") (class "Default")
      (node (ref "IC12") (pin "46") (pinfunction "PF1(OC0B/XCK0/SCL)_46") (pintype "bidirectional"))
      (node (ref "IC17") (pin "4") (pinfunction "O_4") (pintype "tri_state"))
      (node (ref "IC18") (pin "2") (pinfunction "I_2") (pintype "input"))
      (node (ref "R19") (pin "2") (pinfunction "2_2") (pintype "passive"))
    )
    (net (code "40") (name "/IO1_DIR") (class "Default")
      (node (ref "IC12") (pin "81") (pinfunction "PK6(A6/A14/A22)_81") (pintype "bidirectional"))
      (node (ref "IC19") (pin "1") (pinfunction "OE_1") (pintype "input"))
      (node (ref "IC20") (pin "1") (pinfunction "OE_1") (pintype "input"))
      (node (ref "R20") (pin "2") (pinfunction "2_2") (pintype "passive"))
    )
    (net (code "41") (name "/IO1_UC") (class "Default")
      (node (ref "IC12") (pin "76") (pinfunction "PK1(A1/A9/A17)_76") (pintype "bidirectional"))
      (node (ref "IC19") (pin "4") (pinfunction "O_4") (pintype "tri_state"))
      (node (ref "IC20") (pin "2") (pinfunction "I_2") (pintype "input"))
      (node (ref "R21") (pin "2") (pinfunction "2_2") (pintype "passive"))
    )
    (net (code "42") (name "/IO2_DIR") (class "Default")
      (node (ref "IC12") (pin "82") (pinfunction "PK7(A7/A15/A23)_82") (pintype "bidirectional"))
      (node (ref "IC21") (pin "1") (pinfunction "OE_1") (pintype "input"))
      (node (ref "IC22") (pin "1") (pinfunction "OE_1") (pintype "input"))
      (node (ref "R22") (pin "2") (pinfunction "2_2") (pintype "passive"))
    )
    (net (code "43") (name "/IO2_UC") (class "Default")
      (node (ref "IC12") (pin "77") (pinfunction "PK2(A2/A10/A18)_77") (pintype "bidirectional"))
      (node (ref "IC21") (pin "4") (pinfunction "O_4") (pintype "tri_state"))
      (node (ref "IC22") (pin "2") (pinfunction "I_2") (pintype "input"))
      (node (ref "R23") (pin "2") (pinfunction "2_2") (pintype "passive"))
    )
    (net (code "44") (name "/LED_CLOCKIN") (class "Default")
      (node (ref "IC12") (pin "60") (pinfunction "PH5(BA1/~{CS1}/A17)_60") (pintype "bidirectional"))
      (node (ref "R40") (pin "1") (pinfunction "1_1") (pintype "passive"))
    )
    (net (code "45") (name "/LED_CLOCKOUT") (class "Default")
      (node (ref "IC12") (pin "58") (pinfunction "PH3(~{DOM}/ALE2)_58") (pintype "bidirectional"))
      (node (ref "R36") (pin "1") (pinfunction "1_1") (pintype "passive"))
    )
    (net (code "46") (name "/LED_EXPANSION") (class "Default")
      (node (ref "IC12") (pin "57") (pinfunction "PH2(~{RAS}/ALE1)_57") (pintype "bidirectional"))
      (node (ref "R35") (pin "1") (pinfunction "1_1") (pintype "passive"))
    )
    (net (code "47") (name "/LED_IO0") (class "Default")
      (node (ref "IC12") (pin "59") (pinfunction "PH4(BA0/~{CS0}/A16)_59") (pintype "bidirectional"))
      (node (ref "R39") (pin "1") (pinfunction "1_1") (pintype "passive"))
    )
    (net (code "48") (name "/LED_IO1") (class "Default")
      (node (ref "IC12") (pin "61") (pinfunction "PH6(CKE/~{CS2}/A18)_61") (pintype "bidirectional"))
      (node (ref "R43") (pin "1") (pinfunction "1_1") (pintype "passive"))
    )
    (net (code "49") (name "/LED_IO2") (class "Default")
      (node (ref "IC12") (pin "62") (pinfunction "PH7(CLK/~{CS3}/A19)_62") (pintype "bidirectional"))
      (node (ref "R49") (pin "1") (pinfunction "1_1") (pintype "passive"))
    )
    (net (code "50") (name "/LED_POWER") (class "Default")
      (node (ref "IC12") (pin "65") (pinfunction "PJ0(D0/A0/A8)_65") (pintype "bidirectional"))
      (node (ref "R50") (pin "1") (pinfunction "1_1") (pintype "passive"))
    )
    (net (code "51") (name "/MASTER_CTS") (class "Default")
      (node (ref "IC12") (pin "75") (pinfunction "PK0(A0/A8/A16)_75") (pintype "bidirectional"))
      (node (ref "IC2") (pin "4") (pinfunction "A2_4") (pintype "input"))
    )
    (net (code "52") (name "/MASTER_RTS") (class "Default")
      (node (ref "IC12") (pin "71") (pinfunction "PJ6(A10/D6/A6/A14)_71") (pintype "bidirectional"))
      (node (ref "IC2") (pin "12") (pinfunction "Y4_12") (pintype "tri_state"))
    )
    (net (code "53") (name "/MASTER_RXD") (class "Default")
      (node (ref "IC12") (pin "48") (pinfunction "PF3(OC0D/TXD0)_48") (pintype "bidirectional"))
      (node (ref "IC2") (pin "2") (pinfunction "A1_2") (pintype "input"))
    )
    (net (code "54") (name "/MASTER_TXD") (class "Default")
      (node (ref "IC12") (pin "47") (pinfunction "PF2(OC0C/RXD0)_47") (pintype "bidirectional"))
      (node (ref "IC2") (pin "14") (pinfunction "Y3_14") (pintype "tri_state"))
    )
    (net (code "55") (name "/REF2.048V") (class "Default")
      (node (ref "IC12") (pin "5") (pinfunction "PB0(ADCB0/AREFB)_5") (pintype "bidirectional"))
      (node (ref "IC6") (pin "6") (pinfunction "VOUT_6") (pintype "bidirectional"))
    )
    (net (code "56") (name "/RELAY") (class "Default")
      (node (ref "IC12") (pin "78") (pinfunction "PK3(A3/A11/A19)_78") (pintype "bidirectional"))
      (node (ref "R15") (pin "1") (pinfunction "1_1") (pintype "passive"))
    )
    (net (code "57") (name "/STATE") (class "Default")
      (node (ref "IC12") (pin "1") (pinfunction "PA6(ADCA6)_1") (pintype "bidirectional"))
      (node (ref "R44") (pin "1") (pinfunction "1_1") (pintype "passive"))
    )
    (net (code "58") (name "/USER_INPUT") (class "Default")
      (node (ref "C62") (pin "1") (pinfunction "1_1") (pintype "passive"))
      (node (ref "IC12") (pin "17") (pinfunction "PC2(OC0C/RXD0)_17") (pintype "bidirectional"))
      (node (ref "R45") (pin "2") (pinfunction "2_2") (pintype "passive"))
      (node (ref "R48") (pin "1") (pinfunction "1_1") (pintype "passive"))
    )
    (net (code "59") (name "/~{EN_MASTER}") (class "Default")
      (node (ref "IC12") (pin "26") (pinfunction "PD1(OC0B/XCK0/SCL)_26") (pintype "bidirectional"))
      (node (ref "IC2") (pin "1") (pinfunction "G_1") (pintype "input"))
      (node (ref "IC2") (pin "19") (pinfunction "G_19") (pintype "input"))
    )
    (net (code "60") (name "AVCC") (class "Default")
      (node (ref "C12") (pin "+") (pinfunction "+_+") (pintype "passive"))
      (node (ref "C13") (pin "1") (pinfunction "1_1") (pintype "passive"))
      (node (ref "C15") (pin "1") (pinfunction "1_1") (pintype "passive"))
      (node (ref "C17") (pin "1") (pinfunction "1_1") (pintype "passive"))
      (node (ref "C31") (pin "1") (pinfunction "1_1") (pintype "passive"))
      (node (ref "C33") (pin "1") (pinfunction "1_1") (pintype "passive"))
      (node (ref "C35") (pin "1") (pinfunction "1_1") (pintype "passive"))
      (node (ref "C41") (pin "1") (pinfunction "1_1") (pintype "passive"))
      (node (ref "C42") (pin "1") (pinfunction "1_1") (pintype "passive"))
      (node (ref "C43") (pin "1") (pinfunction "1_1") (pintype "passive"))
      (node (ref "C48") (pin "1") (pinfunction "1_1") (pintype "passive"))
      (node (ref "C50") (pin "1") (pinfunction "1_1") (pintype "passive"))
      (node (ref "IC12") (pin "4") (pinfunction "AVCC-B_4") (pintype "power_in"))
      (node (ref "IC12") (pin "94") (pinfunction "AVCC-A_94") (pintype "power_in"))
      (node (ref "IC13") (pin "7") (pinfunction "+VS_7") (pintype "input"))
      (node (ref "IC14") (pin "1") (pinfunction "IN_1") (pintype "bidirectional"))
      (node (ref "IC14") (pin "3") (pinfunction "EN_3") (pintype "bidirectional"))
      (node (ref "IC15") (pin "7") (pinfunction "+VS_7") (pintype "input"))
      (node (ref "IC5") (pin "5") (pinfunction "OUT_5") (pintype "bidirectional"))
      (node (ref "IC6") (pin "2") (pinfunction "VIN_2") (pintype "bidirectional"))
      (node (ref "R16") (pin "2") (pinfunction "2_2") (pintype "passive"))
      (node (ref "R25") (pin "2") (pinfunction "2_2") (pintype "passive"))
      (node (ref "R34") (pin "1") (pinfunction "1_1") (pintype "passive"))
      (node (ref "SENSOR_ANA") (pin "4") (pinfunction "4_4") (pintype "bidirectional"))
    )
    (net (code "61") (name "GND") (class "Default")
      (node (ref "BNC1") (pin "2") (pinfunction "2_2") (pintype "passive"))
      (node (ref "BNC1") (pin "3") (pinfunction "2_3") (pintype "passive"))
      (node (ref "BNC2") (pin "2") (pinfunction "2_2") (pintype "passive"))
      (node (ref "BNC2") (pin "3") (pinfunction "2_3") (pintype "passive"))
      (node (ref "BNC3") (pin "2") (pinfunction "2_2") (pintype "passive"))
      (node (ref "BNC3") (pin "3") (pinfunction "2_3") (pintype "passive"))
      (node (ref "BNC4") (pin "2") (pinfunction "2_2") (pintype "passive"))
      (node (ref "BNC4") (pin "3") (pinfunction "2_3") (pintype "passive"))
      (node (ref "C1") (pin "2") (pinfunction "2_2") (pintype "passive"))
      (node (ref "C10") (pin "2") (pinfunction "2_2") (pintype "passive"))
      (node (ref "C11") (pin "2") (pinfunction "2_2") (pintype "passive"))
      (node (ref "C12") (pin "-") (pinfunction "-_-") (pintype "passive"))
      (node (ref "C13") (pin "2") (pinfunction "2_2") (pintype "passive"))
      (node (ref "C14") (pin "2") (pinfunction "2_2") (pintype "passive"))
      (node (ref "C15") (pin "2") (pinfunction "2_2") (pintype "passive"))
      (node (ref "C16") (pin "2") (pinfunction "2_2") (pintype "passive"))
      (node (ref "C17") (pin "2") (pinfunction "2_2") (pintype "passive"))
      (node (ref "C18") (pin "2") (pinfunction "2_2") (pintype "passive"))
      (node (ref "C19") (pin "2") (pinfunction "2_2") (pintype "passive"))
      (node (ref "C2") (pin "2") (pinfunction "2_2") (pintype "passive"))
      (node (ref "C20") (pin "2") (pinfunction "2_2") (pintype "passive"))
      (node (ref "C21") (pin "2") (pinfunction "2_2") (pintype "passive"))
      (node (ref "C22") (pin "2") (pinfunction "2_2") (pintype "passive"))
      (node (ref "C23") (pin "2") (pinfunction "2_2") (pintype "passive"))
      (node (ref "C24") (pin "2") (pinfunction "2_2") (pintype "passive"))
      (node (ref "C25") (pin "2") (pinfunction "2_2") (pintype "passive"))
      (node (ref "C26") (pin "2") (pinfunction "2_2") (pintype "passive"))
      (node (ref "C27") (pin "2") (pinfunction "2_2") (pintype "passive"))
      (node (ref "C29") (pin "2") (pinfunction "2_2") (pintype "passive"))
      (node (ref "C3") (pin "2") (pinfunction "2_2") (pintype "passive"))
      (node (ref "C30") (pin "2") (pinfunction "2_2") (pintype "passive"))
      (node (ref "C31") (pin "2") (pinfunction "2_2") (pintype "passive"))
      (node (ref "C32") (pin "2") (pinfunction "2_2") (pintype "passive"))
      (node (ref "C33") (pin "2") (pinfunction "2_2") (pintype "passive"))
      (node (ref "C34") (pin "2") (pinfunction "2_2") (pintype "passive"))
      (node (ref "C35") (pin "2") (pinfunction "2_2") (pintype "passive"))
      (node (ref "C36") (pin "2") (pinfunction "2_2") (pintype "passive"))
      (node (ref "C37") (pin "2") (pinfunction "2_2") (pintype "passive"))
      (node (ref "C38") (pin "2") (pinfunction "2_2") (pintype "passive"))
      (node (ref "C39") (pin "2") (pinfunction "2_2") (pintype "passive"))
      (node (ref "C4") (pin "2") (pinfunction "2_2") (pintype "passive"))
      (node (ref "C40") (pin "2") (pinfunction "2_2") (pintype "passive"))
      (node (ref "C41") (pin "2") (pinfunction "2_2") (pintype "passive"))
      (node (ref "C42") (pin "2") (pinfunction "2_2") (pintype "passive"))
      (node (ref "C43") (pin "2") (pinfunction "2_2") (pintype "passive"))
      (node (ref "C44") (pin "2") (pinfunction "2_2") (pintype "passive"))
      (node (ref "C45") (pin "2") (pinfunction "2_2") (pintype "passive"))
      (node (ref "C46") (pin "2") (pinfunction "2_2") (pintype "passive"))
      (node (ref "C47") (pin "2") (pinfunction "2_2") (pintype "passive"))
      (node (ref "C48") (pin "2") (pinfunction "2_2") (pintype "passive"))
      (node (ref "C49") (pin "2") (pinfunction "2_2") (pintype "passive"))
      (node (ref "C5") (pin "2") (pinfunction "2_2") (pintype "passive"))
      (node (ref "C50") (pin "2") (pinfunction "2_2") (pintype "passive"))
      (node (ref "C51") (pin "2") (pinfunction "2_2") (pintype "passive"))
      (node (ref "C52") (pin "2") (pinfunction "2_2") (pintype "passive"))
      (node (ref "C53") (pin "2") (pinfunction "2_2") (pintype "passive"))
      (node (ref "C54") (pin "2") (pinfunction "2_2") (pintype "passive"))
      (node (ref "C55") (pin "2") (pinfunction "2_2") (pintype "passive"))
      (node (ref "C56") (pin "2") (pinfunction "2_2") (pintype "passive"))
      (node (ref "C57") (pin "2") (pinfunction "2_2") (pintype "passive"))
      (node (ref "C58") (pin "1") (pinfunction "1_1") (pintype "passive"))
      (node (ref "C59") (pin "1") (pinfunction "1_1") (pintype "passive"))
      (node (ref "C6") (pin "2") (pinfunction "2_2") (pintype "passive"))
      (node (ref "C60") (pin "2") (pinfunction "2_2") (pintype "passive"))
      (node (ref "C61") (pin "1") (pinfunction "1_1") (pintype "passive"))
      (node (ref "C62") (pin "2") (pinfunction "2_2") (pintype "passive"))
      (node (ref "C7") (pin "2") (pinfunction "2_2") (pintype "passive"))
      (node (ref "C8") (pin "-") (pinfunction "-_-") (pintype "passive"))
      (node (ref "C9") (pin "2") (pinfunction "2_2") (pintype "passive"))
      (node (ref "CLKIN") (pin "5") (pinfunction "5_5") (pintype "passive"))
      (node (ref "IC1") (pin "P$2") (pinfunction "GND_P$2") (pintype "bidirectional"))
      (node (ref "IC10") (pin "4") (pinfunction "AGND_4") (pintype "bidirectional"))
      (node (ref "IC11") (pin "2") (pinfunction "GND_2") (pintype "bidirectional"))
      (node (ref "IC12") (pin "13") (pinfunction "GND_13") (pintype "power_in"))
      (node (ref "IC12") (pin "23") (pinfunction "GND_23") (pintype "power_in"))
      (node (ref "IC12") (pin "3") (pinfunction "GND_3") (pintype "power_in"))
      (node (ref "IC12") (pin "33") (pinfunction "GND_33") (pintype "power_in"))
      (node (ref "IC12") (pin "43") (pinfunction "GND_43") (pintype "power_in"))
      (node (ref "IC12") (pin "53") (pinfunction "GND_53") (pintype "power_in"))
      (node (ref "IC12") (pin "63") (pinfunction "GND_63") (pintype "power_in"))
      (node (ref "IC12") (pin "73") (pinfunction "GND_73") (pintype "power_in"))
      (node (ref "IC12") (pin "84") (pinfunction "GND_84") (pintype "power_in"))
      (node (ref "IC12") (pin "93") (pinfunction "GND_93") (pintype "power_in"))
      (node (ref "IC12") (pin "96") (pinfunction "PA1(ADCA1)_96") (pintype "bidirectional"))
      (node (ref "IC13") (pin "4") (pinfunction "-VS_4") (pintype "input"))
      (node (ref "IC14") (pin "2") (pinfunction "GND_2") (pintype "bidirectional"))
      (node (ref "IC15") (pin "4") (pinfunction "-VS_4") (pintype "input"))
      (node (ref "IC16") (pin "4") (pinfunction "IN-_4") (pintype "input"))
      (node (ref "IC16") (pin "5") (pinfunction "VSS_5") (pintype "power_in"))
      (node (ref "IC17") (pin "3") (pinfunction "GND_3") (pintype "power_in"))
      (node (ref "IC18") (pin "3") (pinfunction "GND_3") (pintype "power_in"))
      (node (ref "IC19") (pin "3") (pinfunction "GND_3") (pintype "power_in"))
      (node (ref "IC2") (pin "10") (pinfunction "GND_10") (pintype "power_in"))
      (node (ref "IC20") (pin "3") (pinfunction "GND_3") (pintype "power_in"))
      (node (ref "IC21") (pin "3") (pinfunction "GND_3") (pintype "power_in"))
      (node (ref "IC22") (pin "3") (pinfunction "GND_3") (pintype "power_in"))
      (node (ref "IC23") (pin "2") (pinfunction "V-_2") (pintype "power_in"))
      (node (ref "IC3") (pin "18") (pinfunction "GND_18") (pintype "power_in"))
      (node (ref "IC3") (pin "21") (pinfunction "GND_21") (pintype "power_in"))
      (node (ref "IC3") (pin "25") (pinfunction "GND_25") (pintype "power_in"))
      (node (ref "IC3") (pin "26") (pinfunction "TEST_26") (pintype "input"))
      (node (ref "IC3") (pin "7") (pinfunction "GND_7") (pintype "power_in"))
      (node (ref "IC4") (pin "2") (pinfunction "GND_2") (pintype "bidirectional"))
      (node (ref "IC5") (pin "2") (pinfunction "GND_2") (pintype "bidirectional"))
      (node (ref "IC6") (pin "4") (pinfunction "GND_4") (pintype "bidirectional"))
      (node (ref "IC7") (pin "18") (pinfunction "GND_18") (pintype "power_in"))
      (node (ref "IC7") (pin "30") (pinfunction "GND_30") (pintype "power_in"))
      (node (ref "IC7") (pin "38") (pinfunction "GND_38") (pintype "power_in"))
      (node (ref "IC7") (pin "8") (pinfunction "GND_8") (pintype "power_in"))
      (node (ref "IC8") (pin "3") (pinfunction "GND_3") (pintype "power_in"))
      (node (ref "IC9") (pin "3") (pinfunction "GND_3") (pintype "power_in"))
      (node (ref "OSC1") (pin "P$2") (pinfunction "GND_P$2") (pintype "passive"))
      (node (ref "OSC2") (pin "P$2") (pinfunction "GND_P$2") (pintype "passive"))
      (node (ref "PDI") (pin "6") (pinfunction "6_6") (pintype "passive"))
      (node (ref "PDI1") (pin "6") (pinfunction "6_6") (pintype "passive"))
      (node (ref "R1") (pin "2") (pinfunction "2_2") (pintype "passive"))
      (node (ref "R12") (pin "2") (pinfunction "2_2") (pintype "passive"))
      (node (ref "R18") (pin "1") (pinfunction "1_1") (pintype "passive"))
      (node (ref "R19") (pin "1") (pinfunction "1_1") (pintype "passive"))
      (node (ref "R2") (pin "1") (pinfunction "1_1") (pintype "passive"))
      (node (ref "R20") (pin "1") (pinfunction "1_1") (pintype "passive"))
      (node (ref "R21") (pin "1") (pinfunction "1_1") (pintype "passive"))
      (node (ref "R22") (pin "1") (pinfunction "1_1") (pintype "passive"))
      (node (ref "R23") (pin "1") (pinfunction "1_1") (pintype "passive"))
      (node (ref "R26") (pin "2") (pinfunction "2_2") (pintype "passive"))
      (node (ref "R27") (pin "2") (pinfunction "2_2") (pintype "passive"))
      (node (ref "R28") (pin "2") (pinfunction "2_2") (pintype "passive"))
      (node (ref "R33") (pin "1") (pinfunction "1_1") (pintype "passive"))
      (node (ref "R5") (pin "1") (pinfunction "1_1") (pintype "passive"))
      (node (ref "SENSOR_ANA") (pin "1") (pinfunction "1_1") (pintype "bidirectional"))
      (node (ref "SENSOR_ANA") (pin "2") (pinfunction "2_2") (pintype "bidirectional"))
      (node (ref "SENSOR_ANA") (pin "SHIELD1") (pinfunction "SHIELD_SHIELD1") (pintype "power_in"))
      (node (ref "SENSOR_ANA") (pin "SHIELD2") (pinfunction "SHIELD_SHIELD2") (pintype "power_in"))
      (node (ref "SENSOR_DIG") (pin "1") (pinfunction "1_1") (pintype "bidirectional"))
      (node (ref "SENSOR_DIG") (pin "SHIELD1") (pinfunction "SHIELD_SHIELD1") (pintype "power_in"))
      (node (ref "SENSOR_DIG") (pin "SHIELD2") (pinfunction "SHIELD_SHIELD2") (pintype "power_in"))
      (node (ref "SV1") (pin "16") (pinfunction "16_16") (pintype "passive"))
      (node (ref "T1") (pin "2") (pinfunction "E_2") (pintype "passive"))
      (node (ref "T2") (pin "2") (pinfunction "E_2") (pintype "passive"))
      (node (ref "T3") (pin "2") (pinfunction "E_2") (pintype "passive"))
      (node (ref "T4") (pin "2") (pinfunction "E_2") (pintype "passive"))
      (node (ref "T5") (pin "2") (pinfunction "E_2") (pintype "passive"))
      (node (ref "T6") (pin "2") (pinfunction "E_2") (pintype "passive"))
      (node (ref "T7") (pin "2") (pinfunction "E_2") (pintype "passive"))
      (node (ref "T8") (pin "2") (pinfunction "E_2") (pintype "passive"))
      (node (ref "T9") (pin "2") (pinfunction "E_2") (pintype "passive"))
      (node (ref "TEST") (pin "1") (pinfunction "3_1") (pintype "passive"))
      (node (ref "USB") (pin "P$5") (pinfunction "5_P$5") (pintype "bidirectional"))
    )
    (net (code "62") (name "Net-(BNC2-Pad1)") (class "Default")
      (node (ref "BNC2") (pin "1") (pinfunction "1_1") (pintype "passive"))
      (node (ref "R29") (pin "2") (pinfunction "2_2") (pintype "passive"))
      (node (ref "R32") (pin "2") (pinfunction "2_2") (pintype "passive"))
    )
    (net (code "63") (name "Net-(BNC3-Pad1)") (class "Default")
      (node (ref "BNC3") (pin "1") (pinfunction "1_1") (pintype "passive"))
      (node (ref "R30") (pin "2") (pinfunction "2_2") (pintype "passive"))
    )
    (net (code "64") (name "Net-(BNC4-Pad1)") (class "Default")
      (node (ref "BNC4") (pin "1") (pinfunction "1_1") (pintype "passive"))
      (node (ref "R31") (pin "2") (pinfunction "2_2") (pintype "passive"))
    )
    (net (code "65") (name "Net-(C3-Pad1)") (class "Default")
      (node (ref "C3") (pin "1") (pinfunction "1_1") (pintype "passive"))
      (node (ref "L1") (pin "2") (pinfunction "2_2") (pintype "passive"))
    )
    (net (code "66") (name "Net-(C44-Pad1)") (class "Default")
      (node (ref "C44") (pin "1") (pinfunction "1_1") (pintype "passive"))
      (node (ref "R13") (pin "1") (pinfunction "1_1") (pintype "passive"))
      (node (ref "R14") (pin "2") (pinfunction "2_2") (pintype "passive"))
    )
    (net (code "67") (name "Net-(C59-Pad2)") (class "Default")
      (node (ref "C59") (pin "2") (pinfunction "2_2") (pintype "passive"))
      (node (ref "R17") (pin "1") (pinfunction "1_1") (pintype "passive"))
      (node (ref "R24") (pin "2") (pinfunction "2_2") (pintype "passive"))
    )
    (net (code "68") (name "Net-(CLKIN-Pad1)") (class "Default")
      (node (ref "CLKIN") (pin "1") (pinfunction "1_1") (pintype "passive"))
      (node (ref "R7") (pin "2") (pinfunction "2_2") (pintype "passive"))
      (node (ref "R8") (pin "1") (pinfunction "1_1") (pintype "passive"))
    )
    (net (code "69") (name "Net-(IC1-VBUS)") (class "Default")
      (node (ref "IC1") (pin "P$5") (pinfunction "VBUS_P$5") (pintype "bidirectional"))
      (node (ref "USB") (pin "P$1") (pinfunction "1_P$1") (pintype "bidirectional"))
    )
    (net (code "70") (name "Net-(IC3-3V3OUT)") (class "Default")
      (node (ref "C7") (pin "1") (pinfunction "1_1") (pintype "passive"))
      (node (ref "IC3") (pin "17") (pinfunction "3V3OUT_17") (pintype "output"))
    )
    (net (code "71") (name "Net-(IC3-USBDM)") (class "Default")
      (node (ref "C6") (pin "1") (pinfunction "1_1") (pintype "passive"))
      (node (ref "IC1") (pin "P$6") (pinfunction "IO1_P$6") (pintype "bidirectional"))
      (node (ref "IC3") (pin "16") (pinfunction "USBDM_16") (pintype "bidirectional"))
    )
    (net (code "72") (name "Net-(IC3-USBDP)") (class "Default")
      (node (ref "C4") (pin "1") (pinfunction "1_1") (pintype "passive"))
      (node (ref "IC1") (pin "P$4") (pinfunction "IO2_P$4") (pintype "bidirectional"))
      (node (ref "IC3") (pin "15") (pinfunction "USBDP_15") (pintype "bidirectional"))
    )
    (net (code "73") (name "Net-(IC7-PDI-DATA)") (class "Default")
      (node (ref "IC7") (pin "34") (pinfunction "PDI-DATA_34") (pintype "bidirectional"))
      (node (ref "PDI1") (pin "1") (pinfunction "1_1") (pintype "passive"))
    )
    (net (code "74") (name "Net-(IC7-PR1{slash}XTAL1)") (class "Default")
      (node (ref "IC7") (pin "37") (pinfunction "PR1/XTAL1_37") (pintype "bidirectional"))
      (node (ref "OSC1") (pin "P$3") (pinfunction "OUTPUT_P$3") (pintype "passive"))
    )
    (net (code "75") (name "Net-(IC7-RESET{slash}PDI-CLK)") (class "Default")
      (node (ref "IC7") (pin "35") (pinfunction "RESET/PDI-CLK_35") (pintype "input"))
      (node (ref "PDI1") (pin "5") (pinfunction "5_5") (pintype "passive"))
    )
    (net (code "76") (name "Net-(IC9A-I)") (class "Default")
      (node (ref "CLKIN") (pin "4") (pinfunction "4_4") (pintype "passive"))
      (node (ref "IC9") (pin "2") (pinfunction "I_2") (pintype "input"))
      (node (ref "R6") (pin "2") (pinfunction "2_2") (pintype "passive"))
      (node (ref "R8") (pin "2") (pinfunction "2_2") (pintype "passive"))
    )
    (net (code "77") (name "Net-(IC10-A1)") (class "Default")
      (node (ref "IC10") (pin "2") (pinfunction "A1_2") (pintype "bidirectional"))
      (node (ref "IC8") (pin "4") (pinfunction "O_4") (pintype "output"))
      (node (ref "R3") (pin "2") (pinfunction "2_2") (pintype "passive"))
      (node (ref "R4") (pin "2") (pinfunction "2_2") (pintype "passive"))
    )
    (net (code "78") (name "Net-(IC10-B1)") (class "Default")
      (node (ref "CLKOUT") (pin "4") (pinfunction "4_4") (pintype "passive"))
      (node (ref "IC10") (pin "6") (pinfunction "B1_6") (pintype "bidirectional"))
    )
    (net (code "79") (name "Net-(IC10-BGND)") (class "Default")
      (node (ref "C28") (pin "2") (pinfunction "2_2") (pintype "passive"))
      (node (ref "CLKOUT") (pin "5") (pinfunction "5_5") (pintype "passive"))
      (node (ref "IC10") (pin "5") (pinfunction "BGND_5") (pintype "bidirectional"))
    )
    (net (code "80") (name "Net-(IC10-BVDD)") (class "Default")
      (node (ref "C28") (pin "1") (pinfunction "1_1") (pintype "passive"))
      (node (ref "CLKOUT") (pin "1") (pinfunction "1_1") (pintype "passive"))
      (node (ref "IC10") (pin "8") (pinfunction "BVDD_8") (pintype "bidirectional"))
    )
    (net (code "81") (name "Net-(IC11-OUT)") (class "Default")
      (node (ref "C27") (pin "1") (pinfunction "1_1") (pintype "passive"))
      (node (ref "IC11") (pin "5") (pinfunction "OUT_5") (pintype "bidirectional"))
      (node (ref "R7") (pin "1") (pinfunction "1_1") (pintype "passive"))
    )
    (net (code "82") (name "Net-(IC12-PDI-CLK{slash}~{RESET})") (class "Default")
      (node (ref "IC12") (pin "90") (pinfunction "PDI-CLK/~{RESET}_90") (pintype "input"))
      (node (ref "PDI") (pin "5") (pinfunction "5_5") (pintype "passive"))
    )
    (net (code "83") (name "Net-(IC12-PDI-DATA)") (class "Default")
      (node (ref "IC12") (pin "89") (pinfunction "PDI-DATA_89") (pintype "bidirectional"))
      (node (ref "PDI") (pin "1") (pinfunction "1_1") (pintype "passive"))
    )
    (net (code "84") (name "Net-(IC12-PR1(XTAL1))") (class "Default")
      (node (ref "IC12") (pin "92") (pinfunction "PR1(XTAL1)_92") (pintype "bidirectional"))
      (node (ref "OSC2") (pin "P$3") (pinfunction "OUTPUT_P$3") (pintype "passive"))
    )
    (net (code "85") (name "Net-(IC13-IN+)") (class "Default")
      (node (ref "IC13") (pin "3") (pinfunction "IN+_3") (pintype "input"))
      (node (ref "R11") (pin "1") (pinfunction "1_1") (pintype "passive"))
      (node (ref "R12") (pin "1") (pinfunction "1_1") (pintype "passive"))
    )
    (net (code "86") (name "Net-(IC13-IN-)") (class "Default")
      (node (ref "IC13") (pin "2") (pinfunction "IN-_2") (pintype "input"))
      (node (ref "IC13") (pin "6") (pinfunction "OUT_6") (pintype "output"))
      (node (ref "R13") (pin "2") (pinfunction "2_2") (pintype "passive"))
    )
    (net (code "87") (name "Net-(IC14-OUT)") (class "Default")
      (node (ref "C49") (pin "1") (pinfunction "1_1") (pintype "passive"))
      (node (ref "IC14") (pin "5") (pinfunction "OUT_5") (pintype "bidirectional"))
      (node (ref "IC16") (pin "2") (pinfunction "AVDD_2") (pintype "power_in"))
    )
    (net (code "88") (name "Net-(IC15-IN+)") (class "Default")
      (node (ref "IC15") (pin "3") (pinfunction "IN+_3") (pintype "input"))
      (node (ref "U1") (pin "5") (pinfunction "IN_5") (pintype "passive"))
    )
    (net (code "89") (name "Net-(IC15-IN-)") (class "Default")
      (node (ref "BNC1") (pin "1") (pinfunction "1_1") (pintype "passive"))
      (node (ref "IC15") (pin "2") (pinfunction "IN-_2") (pintype "input"))
      (node (ref "IC15") (pin "6") (pinfunction "OUT_6") (pintype "output"))
    )
    (net (code "90") (name "Net-(IC16-IN+)") (class "Default")
      (node (ref "C45") (pin "1") (pinfunction "1_1") (pintype "passive"))
      (node (ref "IC16") (pin "3") (pinfunction "IN+_3") (pintype "input"))
      (node (ref "R14") (pin "1") (pinfunction "1_1") (pintype "passive"))
      (node (ref "U1") (pin "1") (pinfunction "NC_1") (pintype "passive"))
    )
    (net (code "91") (name "Net-(IC16-VREF)") (class "Default")
      (node (ref "C46") (pin "1") (pinfunction "1_1") (pintype "passive"))
      (node (ref "C47") (pin "1") (pinfunction "1_1") (pintype "passive"))
      (node (ref "IC16") (pin "1") (pinfunction "VREF_1") (pintype "power_in"))
      (node (ref "R16") (pin "1") (pinfunction "1_1") (pintype "passive"))
    )
    (net (code "92") (name "Net-(IC17A-I)") (class "Default")
      (node (ref "IC17") (pin "2") (pinfunction "I_2") (pintype "input"))
      (node (ref "IC18") (pin "4") (pinfunction "O_4") (pintype "output"))
      (node (ref "R26") (pin "1") (pinfunction "1_1") (pintype "passive"))
      (node (ref "R29") (pin "1") (pinfunction "1_1") (pintype "passive"))
    )
    (net (code "93") (name "Net-(IC19A-I)") (class "Default")
      (node (ref "IC19") (pin "2") (pinfunction "I_2") (pintype "input"))
      (node (ref "IC20") (pin "4") (pinfunction "O_4") (pintype "output"))
      (node (ref "R27") (pin "1") (pinfunction "1_1") (pintype "passive"))
      (node (ref "R30") (pin "1") (pinfunction "1_1") (pintype "passive"))
    )
    (net (code "94") (name "Net-(IC21A-I)") (class "Default")
      (node (ref "IC21") (pin "2") (pinfunction "I_2") (pintype "input"))
      (node (ref "IC22") (pin "4") (pinfunction "O_4") (pintype "output"))
      (node (ref "R28") (pin "1") (pinfunction "1_1") (pintype "passive"))
      (node (ref "R31") (pin "1") (pinfunction "1_1") (pintype "passive"))
    )
    (net (code "95") (name "Net-(IC23-+IN)") (class "Default")
      (node (ref "C61") (pin "2") (pinfunction "2_2") (pintype "passive"))
      (node (ref "IC23") (pin "3") (pinfunction "+IN_3") (pintype "input"))
      (node (ref "R32") (pin "1") (pinfunction "1_1") (pintype "passive"))
      (node (ref "R33") (pin "2") (pinfunction "2_2") (pintype "passive"))
      (node (ref "R34") (pin "2") (pinfunction "2_2") (pintype "passive"))
    )
    (net (code "96") (name "Net-(IC23--IN)") (class "Default")
      (node (ref "IC23") (pin "1") (pinfunction "OUT_1") (pintype "output"))
      (node (ref "IC23") (pin "4") (pinfunction "-IN_4") (pintype "input"))
      (node (ref "R24") (pin "1") (pinfunction "1_1") (pintype "passive"))
    )
    (net (code "97") (name "Net-(IC23-V+)") (class "Default")
      (node (ref "C60") (pin "1") (pinfunction "1_1") (pintype "passive"))
      (node (ref "IC23") (pin "5") (pinfunction "V+_5") (pintype "power_in"))
      (node (ref "R25") (pin "1") (pinfunction "1_1") (pintype "passive"))
    )
    (net (code "98") (name "Net-(LED0A-C)") (class "Default")
      (node (ref "LED0") (pin "C1") (pinfunction "C_C1") (pintype "passive"))
      (node (ref "R38") (pin "1") (pinfunction "1_1") (pintype "passive"))
    )
    (net (code "99") (name "Net-(LED0B-C)") (class "Default")
      (node (ref "LED0") (pin "C2") (pinfunction "C_C2") (pintype "passive"))
      (node (ref "R37") (pin "1") (pinfunction "1_1") (pintype "passive"))
    )
    (net (code "100") (name "Net-(LED1A-C)") (class "Default")
      (node (ref "LED1") (pin "C1") (pinfunction "C_C1") (pintype "passive"))
      (node (ref "R42") (pin "1") (pinfunction "1_1") (pintype "passive"))
    )
    (net (code "101") (name "Net-(LED1B-C)") (class "Default")
      (node (ref "LED1") (pin "C2") (pinfunction "C_C2") (pintype "passive"))
      (node (ref "R41") (pin "1") (pinfunction "1_1") (pintype "passive"))
    )
    (net (code "102") (name "Net-(LED2A-C)") (class "Default")
      (node (ref "LED2") (pin "C1") (pinfunction "C_C1") (pintype "passive"))
      (node (ref "R47") (pin "1") (pinfunction "1_1") (pintype "passive"))
    )
    (net (code "103") (name "Net-(LED2B-C)") (class "Default")
      (node (ref "LED2") (pin "C2") (pinfunction "C_C2") (pintype "passive"))
      (node (ref "R46") (pin "1") (pinfunction "1_1") (pintype "passive"))
    )
    (net (code "104") (name "Net-(LED3A-C)") (class "Default")
      (node (ref "LED3") (pin "C1") (pinfunction "C_C1") (pintype "passive"))
      (node (ref "R52") (pin "1") (pinfunction "1_1") (pintype "passive"))
    )
    (net (code "105") (name "Net-(LED3B-C)") (class "Default")
      (node (ref "LED3") (pin "C2") (pinfunction "C_C2") (pintype "passive"))
      (node (ref "R51") (pin "1") (pinfunction "1_1") (pintype "passive"))
    )
    (net (code "106") (name "Net-(R11-Pad2)") (class "Default")
      (node (ref "R11") (pin "2") (pinfunction "2_2") (pintype "passive"))
      (node (ref "SENSOR_ANA") (pin "3") (pinfunction "3_3") (pintype "bidirectional"))
    )
    (net (code "107") (name "Net-(R45-Pad1)") (class "Default")
      (node (ref "R45") (pin "1") (pinfunction "1_1") (pintype "passive"))
      (node (ref "TEST") (pin "2") (pinfunction "2_2") (pintype "passive"))
    )
    (net (code "108") (name "Net-(T1-B)") (class "Default")
      (node (ref "R15") (pin "2") (pinfunction "2_2") (pintype "passive"))
      (node (ref "T1") (pin "1") (pinfunction "B_1") (pintype "passive"))
    )
    (net (code "109") (name "Net-(T1-C)") (class "Default")
      (node (ref "D1") (pin "A") (pinfunction "A_A") (pintype "passive"))
      (node (ref "T1") (pin "3") (pinfunction "C_3") (pintype "passive"))
      (node (ref "U1") (pin "8") (pinfunction "R-_8") (pintype "passive"))
    )
    (net (code "110") (name "Net-(T2-B)") (class "Default")
      (node (ref "R35") (pin "2") (pinfunction "2_2") (pintype "passive"))
      (node (ref "T2") (pin "1") (pinfunction "B_1") (pintype "passive"))
    )
    (net (code "111") (name "Net-(T2-C)") (class "Default")
      (node (ref "R37") (pin "2") (pinfunction "2_2") (pintype "passive"))
      (node (ref "T2") (pin "3") (pinfunction "C_3") (pintype "passive"))
    )
    (net (code "112") (name "Net-(T3-B)") (class "Default")
      (node (ref "R36") (pin "2") (pinfunction "2_2") (pintype "passive"))
      (node (ref "T3") (pin "1") (pinfunction "B_1") (pintype "passive"))
    )
    (net (code "113") (name "Net-(T3-C)") (class "Default")
      (node (ref "R38") (pin "2") (pinfunction "2_2") (pintype "passive"))
      (node (ref "T3") (pin "3") (pinfunction "C_3") (pintype "passive"))
    )
    (net (code "114") (name "Net-(T4-B)") (class "Default")
      (node (ref "R39") (pin "2") (pinfunction "2_2") (pintype "passive"))
      (node (ref "T4") (pin "1") (pinfunction "B_1") (pintype "passive"))
    )
    (net (code "115") (name "Net-(T4-C)") (class "Default")
      (node (ref "R41") (pin "2") (pinfunction "2_2") (pintype "passive"))
      (node (ref "T4") (pin "3") (pinfunction "C_3") (pintype "passive"))
    )
    (net (code "116") (name "Net-(T5-B)") (class "Default")
      (node (ref "R40") (pin "2") (pinfunction "2_2") (pintype "passive"))
      (node (ref "T5") (pin "1") (pinfunction "B_1") (pintype "passive"))
    )
    (net (code "117") (name "Net-(T5-C)") (class "Default")
      (node (ref "R42") (pin "2") (pinfunction "2_2") (pintype "passive"))
      (node (ref "T5") (pin "3") (pinfunction "C_3") (pintype "passive"))
    )
    (net (code "118") (name "Net-(T6-B)") (class "Default")
      (node (ref "R43") (pin "2") (pinfunction "2_2") (pintype "passive"))
      (node (ref "T6") (pin "1") (pinfunction "B_1") (pintype "passive"))
    )
    (net (code "119") (name "Net-(T6-C)") (class "Default")
      (node (ref "R46") (pin "2") (pinfunction "2_2") (pintype "passive"))
      (node (ref "T6") (pin "3") (pinfunction "C_3") (pintype "passive"))
    )
    (net (code "120") (name "Net-(T7-B)") (class "Default")
      (node (ref "R44") (pin "2") (pinfunction "2_2") (pintype "passive"))
      (node (ref "T7") (pin "1") (pinfunction "B_1") (pintype "passive"))
    )
    (net (code "121") (name "Net-(T7-C)") (class "Default")
      (node (ref "R47") (pin "2") (pinfunction "2_2") (pintype "passive"))
      (node (ref "T7") (pin "3") (pinfunction "C_3") (pintype "passive"))
    )
    (net (code "122") (name "Net-(T8-B)") (class "Default")
      (node (ref "R49") (pin "2") (pinfunction "2_2") (pintype "passive"))
      (node (ref "T8") (pin "1") (pinfunction "B_1") (pintype "passive"))
    )
    (net (code "123") (name "Net-(T8-C)") (class "Default")
      (node (ref "R51") (pin "2") (pinfunction "2_2") (pintype "passive"))
      (node (ref "T8") (pin "3") (pinfunction "C_3") (pintype "passive"))
    )
    (net (code "124") (name "Net-(T9-B)") (class "Default")
      (node (ref "R50") (pin "2") (pinfunction "2_2") (pintype "passive"))
      (node (ref "T9") (pin "1") (pinfunction "B_1") (pintype "passive"))
    )
    (net (code "125") (name "Net-(T9-C)") (class "Default")
      (node (ref "R52") (pin "2") (pinfunction "2_2") (pintype "passive"))
      (node (ref "T9") (pin "3") (pinfunction "C_3") (pintype "passive"))
    )
    (net (code "126") (name "Net-(USB-2)") (class "Default")
      (node (ref "IC1") (pin "P$1") (pinfunction "IO1_P$1") (pintype "bidirectional"))
      (node (ref "USB") (pin "P$2") (pinfunction "2_P$2") (pintype "bidirectional"))
    )
    (net (code "127") (name "Net-(USB-3)") (class "Default")
      (node (ref "IC1") (pin "P$3") (pinfunction "IO2_P$3") (pintype "bidirectional"))
      (node (ref "USB") (pin "P$3") (pinfunction "3_P$3") (pintype "bidirectional"))
    )
    (net (code "128") (name "Net-(USB-P$1)") (class "Default")
      (node (ref "R1") (pin "1") (pinfunction "1_1") (pintype "passive"))
      (node (ref "USB") (pin "SHIELD_1") (pinfunction "P$1_SHIELD_1") (pintype "bidirectional"))
    )
    (net (code "129") (name "Net-(USB-P$4)") (class "Default")
      (node (ref "C1") (pin "1") (pinfunction "1_1") (pintype "passive"))
      (node (ref "USB") (pin "SHIELD_4") (pinfunction "P$4_SHIELD_4") (pintype "bidirectional"))
    )
    (net (code "130") (name "VCC") (class "Default")
      (node (ref "C14") (pin "1") (pinfunction "1_1") (pintype "passive"))
      (node (ref "C16") (pin "1") (pinfunction "1_1") (pintype "passive"))
      (node (ref "C18") (pin "1") (pinfunction "1_1") (pintype "passive"))
      (node (ref "C19") (pin "1") (pinfunction "1_1") (pintype "passive"))
      (node (ref "C2") (pin "1") (pinfunction "1_1") (pintype "passive"))
      (node (ref "C20") (pin "1") (pinfunction "1_1") (pintype "passive"))
      (node (ref "C21") (pin "1") (pinfunction "1_1") (pintype "passive"))
      (node (ref "C22") (pin "1") (pinfunction "1_1") (pintype "passive"))
      (node (ref "C23") (pin "1") (pinfunction "1_1") (pintype "passive"))
      (node (ref "C24") (pin "1") (pinfunction "1_1") (pintype "passive"))
      (node (ref "C25") (pin "1") (pinfunction "1_1") (pintype "passive"))
      (node (ref "C29") (pin "1") (pinfunction "1_1") (pintype "passive"))
      (node (ref "C30") (pin "1") (pinfunction "1_1") (pintype "passive"))
      (node (ref "C32") (pin "1") (pinfunction "1_1") (pintype "passive"))
      (node (ref "C34") (pin "1") (pinfunction "1_1") (pintype "passive"))
      (node (ref "C36") (pin "1") (pinfunction "1_1") (pintype "passive"))
      (node (ref "C37") (pin "1") (pinfunction "1_1") (pintype "passive"))
      (node (ref "C38") (pin "1") (pinfunction "1_1") (pintype "passive"))
      (node (ref "C39") (pin "1") (pinfunction "1_1") (pintype "passive"))
      (node (ref "C40") (pin "1") (pinfunction "1_1") (pintype "passive"))
      (node (ref "C51") (pin "1") (pinfunction "1_1") (pintype "passive"))
      (node (ref "C52") (pin "1") (pinfunction "1_1") (pintype "passive"))
      (node (ref "C54") (pin "1") (pinfunction "1_1") (pintype "passive"))
      (node (ref "C56") (pin "1") (pinfunction "1_1") (pintype "passive"))
      (node (ref "C9") (pin "1") (pinfunction "1_1") (pintype "passive"))
      (node (ref "IC10") (pin "1") (pinfunction "AVDD_1") (pintype "bidirectional"))
      (node (ref "IC12") (pin "14") (pinfunction "VCC_14") (pintype "power_in"))
      (node (ref "IC12") (pin "24") (pinfunction "VCC_24") (pintype "power_in"))
      (node (ref "IC12") (pin "34") (pinfunction "VCC_34") (pintype "power_in"))
      (node (ref "IC12") (pin "44") (pinfunction "VCC_44") (pintype "power_in"))
      (node (ref "IC12") (pin "54") (pinfunction "VCC_54") (pintype "power_in"))
      (node (ref "IC12") (pin "64") (pinfunction "VCC_64") (pintype "power_in"))
      (node (ref "IC12") (pin "74") (pinfunction "VCC_74") (pintype "power_in"))
      (node (ref "IC12") (pin "83") (pinfunction "VCC_83") (pintype "power_in"))
      (node (ref "IC16") (pin "10") (pinfunction "DVIO_10") (pintype "power_in"))
      (node (ref "IC16") (pin "9") (pinfunction "SDI_9") (pintype "input"))
      (node (ref "IC17") (pin "5") (pinfunction "VCC_5") (pintype "power_in"))
      (node (ref "IC19") (pin "5") (pinfunction "VCC_5") (pintype "power_in"))
      (node (ref "IC2") (pin "20") (pinfunction "VCC_20") (pintype "power_in"))
      (node (ref "IC21") (pin "5") (pinfunction "VCC_5") (pintype "power_in"))
      (node (ref "IC3") (pin "4") (pinfunction "VCCIO_4") (pintype "power_in"))
      (node (ref "IC4") (pin "5") (pinfunction "OUT_5") (pintype "bidirectional"))
      (node (ref "IC7") (pin "19") (pinfunction "VCC_19") (pintype "power_in"))
      (node (ref "IC7") (pin "31") (pinfunction "VCC_31") (pintype "power_in"))
      (node (ref "IC7") (pin "39") (pinfunction "AVCC_39") (pintype "power_in"))
      (node (ref "IC7") (pin "9") (pinfunction "VCC_9") (pintype "power_in"))
      (node (ref "IC8") (pin "5") (pinfunction "VCC_5") (pintype "power_in"))
      (node (ref "IC9") (pin "5") (pinfunction "VCC_5") (pintype "power_in"))
      (node (ref "LED0") (pin "A1") (pinfunction "A_A1") (pintype "passive"))
      (node (ref "LED0") (pin "A2") (pinfunction "A_A2") (pintype "passive"))
      (node (ref "LED1") (pin "A1") (pinfunction "A_A1") (pintype "passive"))
      (node (ref "LED1") (pin "A2") (pinfunction "A_A2") (pintype "passive"))
      (node (ref "LED2") (pin "A1") (pinfunction "A_A1") (pintype "passive"))
      (node (ref "LED2") (pin "A2") (pinfunction "A_A2") (pintype "passive"))
      (node (ref "LED3") (pin "A1") (pinfunction "A_A1") (pintype "passive"))
      (node (ref "LED3") (pin "A2") (pinfunction "A_A2") (pintype "passive"))
      (node (ref "OSC1") (pin "P$4") (pinfunction "VDD_P$4") (pintype "passive"))
      (node (ref "OSC2") (pin "P$4") (pinfunction "VDD_P$4") (pintype "passive"))
      (node (ref "PDI") (pin "2") (pinfunction "2_2") (pintype "passive"))
      (node (ref "PDI1") (pin "2") (pinfunction "2_2") (pintype "passive"))
      (node (ref "R10") (pin "1") (pinfunction "1_1") (pintype "passive"))
      (node (ref "R48") (pin "2") (pinfunction "2_2") (pintype "passive"))
      (node (ref "R9") (pin "1") (pinfunction "1_1") (pintype "passive"))
      (node (ref "SENSOR_DIG") (pin "4") (pinfunction "4_4") (pintype "bidirectional"))
    )
    (net (code "131") (name "unconnected-(IC3-CBUS0-Pad23)") (class "Default")
      (node (ref "IC3") (pin "23") (pinfunction "CBUS0_23") (pintype "bidirectional"))
    )
    (net (code "132") (name "unconnected-(IC3-CBUS1-Pad22)") (class "Default")
      (node (ref "IC3") (pin "22") (pinfunction "CBUS1_22") (pintype "bidirectional"))
    )
    (net (code "133") (name "unconnected-(IC3-CBUS2-Pad13)") (class "Default")
      (node (ref "IC3") (pin "13") (pinfunction "CBUS2_13") (pintype "bidirectional"))
    )
    (net (code "134") (name "unconnected-(IC3-CBUS3-Pad14)") (class "Default")
      (node (ref "IC3") (pin "14") (pinfunction "CBUS3_14") (pintype "bidirectional"))
    )
    (net (code "135") (name "unconnected-(IC3-CBUS4-Pad12)") (class "Default")
      (node (ref "IC3") (pin "12") (pinfunction "CBUS4_12") (pintype "bidirectional"))
    )
    (net (code "136") (name "unconnected-(IC3-OSCI-Pad27)") (class "Default")
      (node (ref "IC3") (pin "27") (pinfunction "OSCI_27") (pintype "input"))
    )
    (net (code "137") (name "unconnected-(IC3-OSCO-Pad28)") (class "Default")
      (node (ref "IC3") (pin "28") (pinfunction "OSCO_28") (pintype "output"))
    )
    (net (code "138") (name "unconnected-(IC3-~{DCD}-Pad10)") (class "Default")
      (node (ref "IC3") (pin "10") (pinfunction "~{DCD}_10") (pintype "input"))
    )
    (net (code "139") (name "unconnected-(IC3-~{DSR}-Pad9)") (class "Default")
      (node (ref "IC3") (pin "9") (pinfunction "~{DSR}_9") (pintype "input"))
    )
    (net (code "140") (name "unconnected-(IC3-~{DTR}-Pad2)") (class "Default")
      (node (ref "IC3") (pin "2") (pinfunction "~{DTR}_2") (pintype "output"))
    )
    (net (code "141") (name "unconnected-(IC3-~{RESET}-Pad19)") (class "Default")
      (node (ref "IC3") (pin "19") (pinfunction "~{RESET}_19") (pintype "input"))
    )
    (net (code "142") (name "unconnected-(IC3-~{RI}-Pad6)") (class "Default")
      (node (ref "IC3") (pin "6") (pinfunction "~{RI}_6") (pintype "input"))
    )
    (net (code "143") (name "unconnected-(IC4-N{slash}C-Pad4)") (class "Default")
      (node (ref "IC4") (pin "4") (pinfunction "N/C_4") (pintype "bidirectional"))
    )
    (net (code "144") (name "unconnected-(IC5-N{slash}C-Pad4)") (class "Default")
      (node (ref "IC5") (pin "4") (pinfunction "N/C_4") (pintype "bidirectional"))
    )
    (net (code "145") (name "unconnected-(IC7-PA0{slash}ADC0{slash}AREF-Pad40)") (class "Default")
      (node (ref "IC7") (pin "40") (pinfunction "PA0/ADC0/AREF_40") (pintype "bidirectional"))
    )
    (net (code "146") (name "unconnected-(IC7-PA1{slash}ADC1-Pad41)") (class "Default")
      (node (ref "IC7") (pin "41") (pinfunction "PA1/ADC1_41") (pintype "bidirectional"))
    )
    (net (code "147") (name "unconnected-(IC7-PA2{slash}ADC2-Pad42)") (class "Default")
      (node (ref "IC7") (pin "42") (pinfunction "PA2/ADC2_42") (pintype "bidirectional"))
    )
    (net (code "148") (name "unconnected-(IC7-PA3{slash}ADC3-Pad43)") (class "Default")
      (node (ref "IC7") (pin "43") (pinfunction "PA3/ADC3_43") (pintype "bidirectional"))
    )
    (net (code "149") (name "unconnected-(IC7-PA4{slash}ADC4-Pad44)") (class "Default")
      (node (ref "IC7") (pin "44") (pinfunction "PA4/ADC4_44") (pintype "bidirectional"))
    )
    (net (code "150") (name "unconnected-(IC7-PA5{slash}ADC5-Pad1)") (class "Default")
      (node (ref "IC7") (pin "1") (pinfunction "PA5/ADC5_1") (pintype "bidirectional"))
    )
    (net (code "151") (name "unconnected-(IC7-PA6{slash}ADC6-Pad2)") (class "Default")
      (node (ref "IC7") (pin "2") (pinfunction "PA6/ADC6_2") (pintype "bidirectional"))
    )
    (net (code "152") (name "unconnected-(IC7-PA7{slash}ADC7{slash}AC0-OUT-Pad3)") (class "Default")
      (node (ref "IC7") (pin "3") (pinfunction "PA7/ADC7/AC0-OUT_3") (pintype "bidirectional"))
    )
    (net (code "153") (name "unconnected-(IC7-PB0{slash}ADC8{slash}AREF-Pad4)") (class "Default")
      (node (ref "IC7") (pin "4") (pinfunction "PB0/ADC8/AREF_4") (pintype "bidirectional"))
    )
    (net (code "154") (name "unconnected-(IC7-PB1{slash}ADC9-Pad5)") (class "Default")
      (node (ref "IC7") (pin "5") (pinfunction "PB1/ADC9_5") (pintype "bidirectional"))
    )
    (net (code "155") (name "unconnected-(IC7-PB2{slash}ADC10{slash}DAC0-Pad6)") (class "Default")
      (node (ref "IC7") (pin "6") (pinfunction "PB2/ADC10/DAC0_6") (pintype "bidirectional"))
    )
    (net (code "156") (name "unconnected-(IC7-PB3{slash}ADC11{slash}DAC1-Pad7)") (class "Default")
      (node (ref "IC7") (pin "7") (pinfunction "PB3/ADC11/DAC1_7") (pintype "bidirectional"))
    )
    (net (code "157") (name "unconnected-(IC7-PC0{slash}OC0A{slash}SDA-Pad10)") (class "Default")
      (node (ref "IC7") (pin "10") (pinfunction "PC0/OC0A/SDA_10") (pintype "bidirectional"))
    )
    (net (code "158") (name "unconnected-(IC7-PC1{slash}OC0B{slash}XCK0{slash}SCL-Pad11)") (class "Default")
      (node (ref "IC7") (pin "11") (pinfunction "PC1/OC0B/XCK0/SCL_11") (pintype "bidirectional"))
    )
    (net (code "159") (name "unconnected-(IC7-PC3{slash}OC0D{slash}TXD0-Pad13)") (class "Default")
      (node (ref "IC7") (pin "13") (pinfunction "PC3/OC0D/TXD0_13") (pintype "bidirectional"))
    )
    (net (code "160") (name "unconnected-(IC7-PC4{slash}OC1A{slash}#SS-Pad14)") (class "Default")
      (node (ref "IC7") (pin "14") (pinfunction "PC4/OC1A/#SS_14") (pintype "bidirectional"))
    )
    (net (code "161") (name "unconnected-(IC7-PC5{slash}OC1B{slash}MOSI{slash}XCK1-Pad15)") (class "Default")
      (node (ref "IC7") (pin "15") (pinfunction "PC5/OC1B/MOSI/XCK1_15") (pintype "bidirectional"))
    )
    (net (code "162") (name "unconnected-(IC7-PC6{slash}MISO{slash}RXD1-Pad16)") (class "Default")
      (node (ref "IC7") (pin "16") (pinfunction "PC6/MISO/RXD1_16") (pintype "bidirectional"))
    )
    (net (code "163") (name "unconnected-(IC7-PC7{slash}SCK{slash}TXD1{slash}CLKO{slash}EVO-Pad17)") (class "Default")
      (node (ref "IC7") (pin "17") (pinfunction "PC7/SCK/TXD1/CLKO/EVO_17") (pintype "bidirectional"))
    )
    (net (code "164") (name "unconnected-(IC7-PR0{slash}XTAL2-Pad36)") (class "Default")
      (node (ref "IC7") (pin "36") (pinfunction "PR0/XTAL2_36") (pintype "bidirectional"))
    )
    (net (code "165") (name "unconnected-(IC7-~OC0BXCK0PD1-Pad21)") (class "Default")
      (node (ref "IC7") (pin "21") (pinfunction "~OC0BXCK0PD1_21") (pintype "bidirectional"))
    )
    (net (code "166") (name "unconnected-(IC7-~RXD1MISOPD6-Pad26)") (class "Default")
      (node (ref "IC7") (pin "26") (pinfunction "~RXD1MISOPD6_26") (pintype "bidirectional"))
    )
    (net (code "167") (name "unconnected-(IC7-~XCK1MOSIPD5-Pad25)") (class "Default")
      (node (ref "IC7") (pin "25") (pinfunction "~XCK1MOSIPD5_25") (pintype "bidirectional"))
    )
    (net (code "168") (name "unconnected-(IC7-~{#SSPD4}-Pad24)") (class "Default")
      (node (ref "IC7") (pin "24") (pinfunction "~{#SSPD4}_24") (pintype "bidirectional"))
    )
    (net (code "169") (name "unconnected-(IC7-~{OC0APD0}-Pad20)") (class "Default")
      (node (ref "IC7") (pin "20") (pinfunction "~{OC0APD0}_20") (pintype "bidirectional"))
    )
    (net (code "170") (name "unconnected-(IC10-AVDD{slash}NC-Pad3)") (class "Default")
      (node (ref "IC10") (pin "3") (pinfunction "AVDD/NC_3") (pintype "bidirectional"))
    )
    (net (code "171") (name "unconnected-(IC10-BGND{slash}NC-Pad7)") (class "Default")
      (node (ref "IC10") (pin "7") (pinfunction "BGND/NC_7") (pintype "bidirectional"))
    )
    (net (code "172") (name "unconnected-(IC11-N{slash}C-Pad4)") (class "Default")
      (node (ref "IC11") (pin "4") (pinfunction "N/C_4") (pintype "bidirectional"))
    )
    (net (code "173") (name "unconnected-(IC12-PA2(ADCA2)-Pad97)") (class "Default")
      (node (ref "IC12") (pin "97") (pinfunction "PA2(ADCA2)_97") (pintype "bidirectional"))
    )
    (net (code "174") (name "unconnected-(IC12-PA3(ADCA3)-Pad98)") (class "Default")
      (node (ref "IC12") (pin "98") (pinfunction "PA3(ADCA3)_98") (pintype "bidirectional"))
    )
    (net (code "175") (name "unconnected-(IC12-PA4(ADCA4)-Pad99)") (class "Default")
      (node (ref "IC12") (pin "99") (pinfunction "PA4(ADCA4)_99") (pintype "bidirectional"))
    )
    (net (code "176") (name "unconnected-(IC12-PA5(ADCA5)-Pad100)") (class "Default")
      (node (ref "IC12") (pin "100") (pinfunction "PA5(ADCA5)_100") (pintype "bidirectional"))
    )
    (net (code "177") (name "unconnected-(IC12-PA7{slash}(ADCA7{slash}AC0-OUT)-Pad2)") (class "Default")
      (node (ref "IC12") (pin "2") (pinfunction "PA7/(ADCA7/AC0-OUT)_2") (pintype "bidirectional"))
    )
    (net (code "178") (name "unconnected-(IC12-PB1(ADCB1)-Pad6)") (class "Default")
      (node (ref "IC12") (pin "6") (pinfunction "PB1(ADCB1)_6") (pintype "bidirectional"))
    )
    (net (code "179") (name "unconnected-(IC12-PB3(ADCB3{slash}DAC1)-Pad8)") (class "Default")
      (node (ref "IC12") (pin "8") (pinfunction "PB3(ADCB3/DAC1)_8") (pintype "bidirectional"))
    )
    (net (code "180") (name "unconnected-(IC12-PB4(ADCB4{slash}TMS)-Pad9)") (class "Default")
      (node (ref "IC12") (pin "9") (pinfunction "PB4(ADCB4/TMS)_9") (pintype "bidirectional"))
    )
    (net (code "181") (name "unconnected-(IC12-PB5(ADCB5{slash}TDI)-Pad10)") (class "Default")
      (node (ref "IC12") (pin "10") (pinfunction "PB5(ADCB5/TDI)_10") (pintype "bidirectional"))
    )
    (net (code "182") (name "unconnected-(IC12-PB6(ADCB6{slash}TCK)-Pad11)") (class "Default")
      (node (ref "IC12") (pin "11") (pinfunction "PB6(ADCB6/TCK)_11") (pintype "bidirectional"))
    )
    (net (code "183") (name "unconnected-(IC12-PB7(ADCB7{slash}AC0-OUT{slash}TDO)-Pad12)") (class "Default")
      (node (ref "IC12") (pin "12") (pinfunction "PB7(ADCB7/AC0-OUT/TDO)_12") (pintype "bidirectional"))
    )
    (net (code "184") (name "unconnected-(IC12-PC1(OC0B{slash}XCK0{slash}SCL)-Pad16)") (class "Default")
      (node (ref "IC12") (pin "16") (pinfunction "PC1(OC0B/XCK0/SCL)_16") (pintype "bidirectional"))
    )
    (net (code "185") (name "unconnected-(IC12-PC3(OC0D{slash}TXD0)-Pad18)") (class "Default")
      (node (ref "IC12") (pin "18") (pinfunction "PC3(OC0D/TXD0)_18") (pintype "bidirectional"))
    )
    (net (code "186") (name "unconnected-(IC12-PC4(OC1A{slash}~{SS})-Pad19)") (class "Default")
      (node (ref "IC12") (pin "19") (pinfunction "PC4(OC1A/~{SS})_19") (pintype "bidirectional"))
    )
    (net (code "187") (name "unconnected-(IC12-PC5(OC1B{slash}MOSI{slash}XCK1)-Pad20)") (class "Default")
      (node (ref "IC12") (pin "20") (pinfunction "PC5(OC1B/MOSI/XCK1)_20") (pintype "bidirectional"))
    )
    (net (code "188") (name "unconnected-(IC12-PE1(OC0B{slash}XCK0{slash}SCL)-Pad36)") (class "Default")
      (node (ref "IC12") (pin "36") (pinfunction "PE1(OC0B/XCK0/SCL)_36") (pintype "bidirectional"))
    )
    (net (code "189") (name "unconnected-(IC12-PE2(OC0C{slash}RXD0)-Pad37)") (class "Default")
      (node (ref "IC12") (pin "37") (pinfunction "PE2(OC0C/RXD0)_37") (pintype "bidirectional"))
    )
    (net (code "190") (name "unconnected-(IC12-PE3(OC0D{slash}TXD0)-Pad38)") (class "Default")
      (node (ref "IC12") (pin "38") (pinfunction "PE3(OC0D/TXD0)_38") (pintype "bidirectional"))
    )
    (net (code "191") (name "unconnected-(IC12-PF6(RXD1{slash}MISO)-Pad51)") (class "Default")
      (node (ref "IC12") (pin "51") (pinfunction "PF6(RXD1/MISO)_51") (pintype "bidirectional"))
    )
    (net (code "192") (name "unconnected-(IC12-PJ7(A11{slash}D7{slash}A7{slash}A15)-Pad72)") (class "Default")
      (node (ref "IC12") (pin "72") (pinfunction "PJ7(A11/D7/A7/A15)_72") (pintype "bidirectional"))
    )
    (net (code "193") (name "unconnected-(IC12-PK4(A4{slash}A12{slash}A20)-Pad79)") (class "Default")
      (node (ref "IC12") (pin "79") (pinfunction "PK4(A4/A12/A20)_79") (pintype "bidirectional"))
    )
    (net (code "194") (name "unconnected-(IC12-PQ0(TOSC1)-Pad85)") (class "Default")
      (node (ref "IC12") (pin "85") (pinfunction "PQ0(TOSC1)_85") (pintype "bidirectional"))
    )
    (net (code "195") (name "unconnected-(IC12-PQ1(TOSC2)-Pad86)") (class "Default")
      (node (ref "IC12") (pin "86") (pinfunction "PQ1(TOSC2)_86") (pintype "bidirectional"))
    )
    (net (code "196") (name "unconnected-(IC12-PQ2-Pad87)") (class "Default")
      (node (ref "IC12") (pin "87") (pinfunction "PQ2_87") (pintype "bidirectional"))
    )
    (net (code "197") (name "unconnected-(IC12-PQ3-Pad88)") (class "Default")
      (node (ref "IC12") (pin "88") (pinfunction "PQ3_88") (pintype "bidirectional"))
    )
    (net (code "198") (name "unconnected-(IC12-PR0(XTAL2)-Pad91)") (class "Default")
      (node (ref "IC12") (pin "91") (pinfunction "PR0(XTAL2)_91") (pintype "bidirectional"))
    )
    (net (code "199") (name "unconnected-(IC14-N{slash}C-Pad4)") (class "Default")
      (node (ref "IC14") (pin "4") (pinfunction "N/C_4") (pintype "bidirectional"))
    )
    (net (code "200") (name "unconnected-(OSC1-STANDBY#-PadP$1)") (class "Default")
      (node (ref "OSC1") (pin "P$1") (pinfunction "STANDBY#_P$1") (pintype "passive"))
    )
    (net (code "201") (name "unconnected-(OSC2-STANDBY#-PadP$1)") (class "Default")
      (node (ref "OSC2") (pin "P$1") (pinfunction "STANDBY#_P$1") (pintype "passive"))
    )
    (net (code "202") (name "unconnected-(PDI-Pad3)") (class "Default")
      (node (ref "PDI") (pin "3") (pinfunction "3_3") (pintype "passive"))
    )
    (net (code "203") (name "unconnected-(PDI-Pad4)") (class "Default")
      (node (ref "PDI") (pin "4") (pinfunction "4_4") (pintype "passive"))
    )
    (net (code "204") (name "unconnected-(PDI1-Pad3)") (class "Default")
      (node (ref "PDI1") (pin "3") (pinfunction "3_3") (pintype "passive"))
    )
    (net (code "205") (name "unconnected-(PDI1-Pad4)") (class "Default")
      (node (ref "PDI1") (pin "4") (pinfunction "4_4") (pintype "passive"))
    )
    (net (code "206") (name "unconnected-(TEST-1-Pad3)") (class "Default")
      (node (ref "TEST") (pin "3") (pinfunction "1_3") (pintype "passive"))
    )
    (net (code "207") (name "unconnected-(USB-4-PadP$4)") (class "Default")
      (node (ref "USB") (pin "P$4") (pinfunction "4_P$4") (pintype "bidirectional"))
    )
    (net (code "208") (name "unconnected-(USB-P$2-PadSHIELD_2)") (class "Default")
      (node (ref "USB") (pin "SHIELD_2") (pinfunction "P$2_SHIELD_2") (pintype "bidirectional"))
    )
    (net (code "209") (name "unconnected-(USB-P$3-PadSHIELD_3)") (class "Default")
      (node (ref "USB") (pin "SHIELD_3") (pinfunction "P$3_SHIELD_3") (pintype "bidirectional"))
    )
  )
)
